# DM01x2.net
KiCad netlist of a schematic drawn in EAGLE
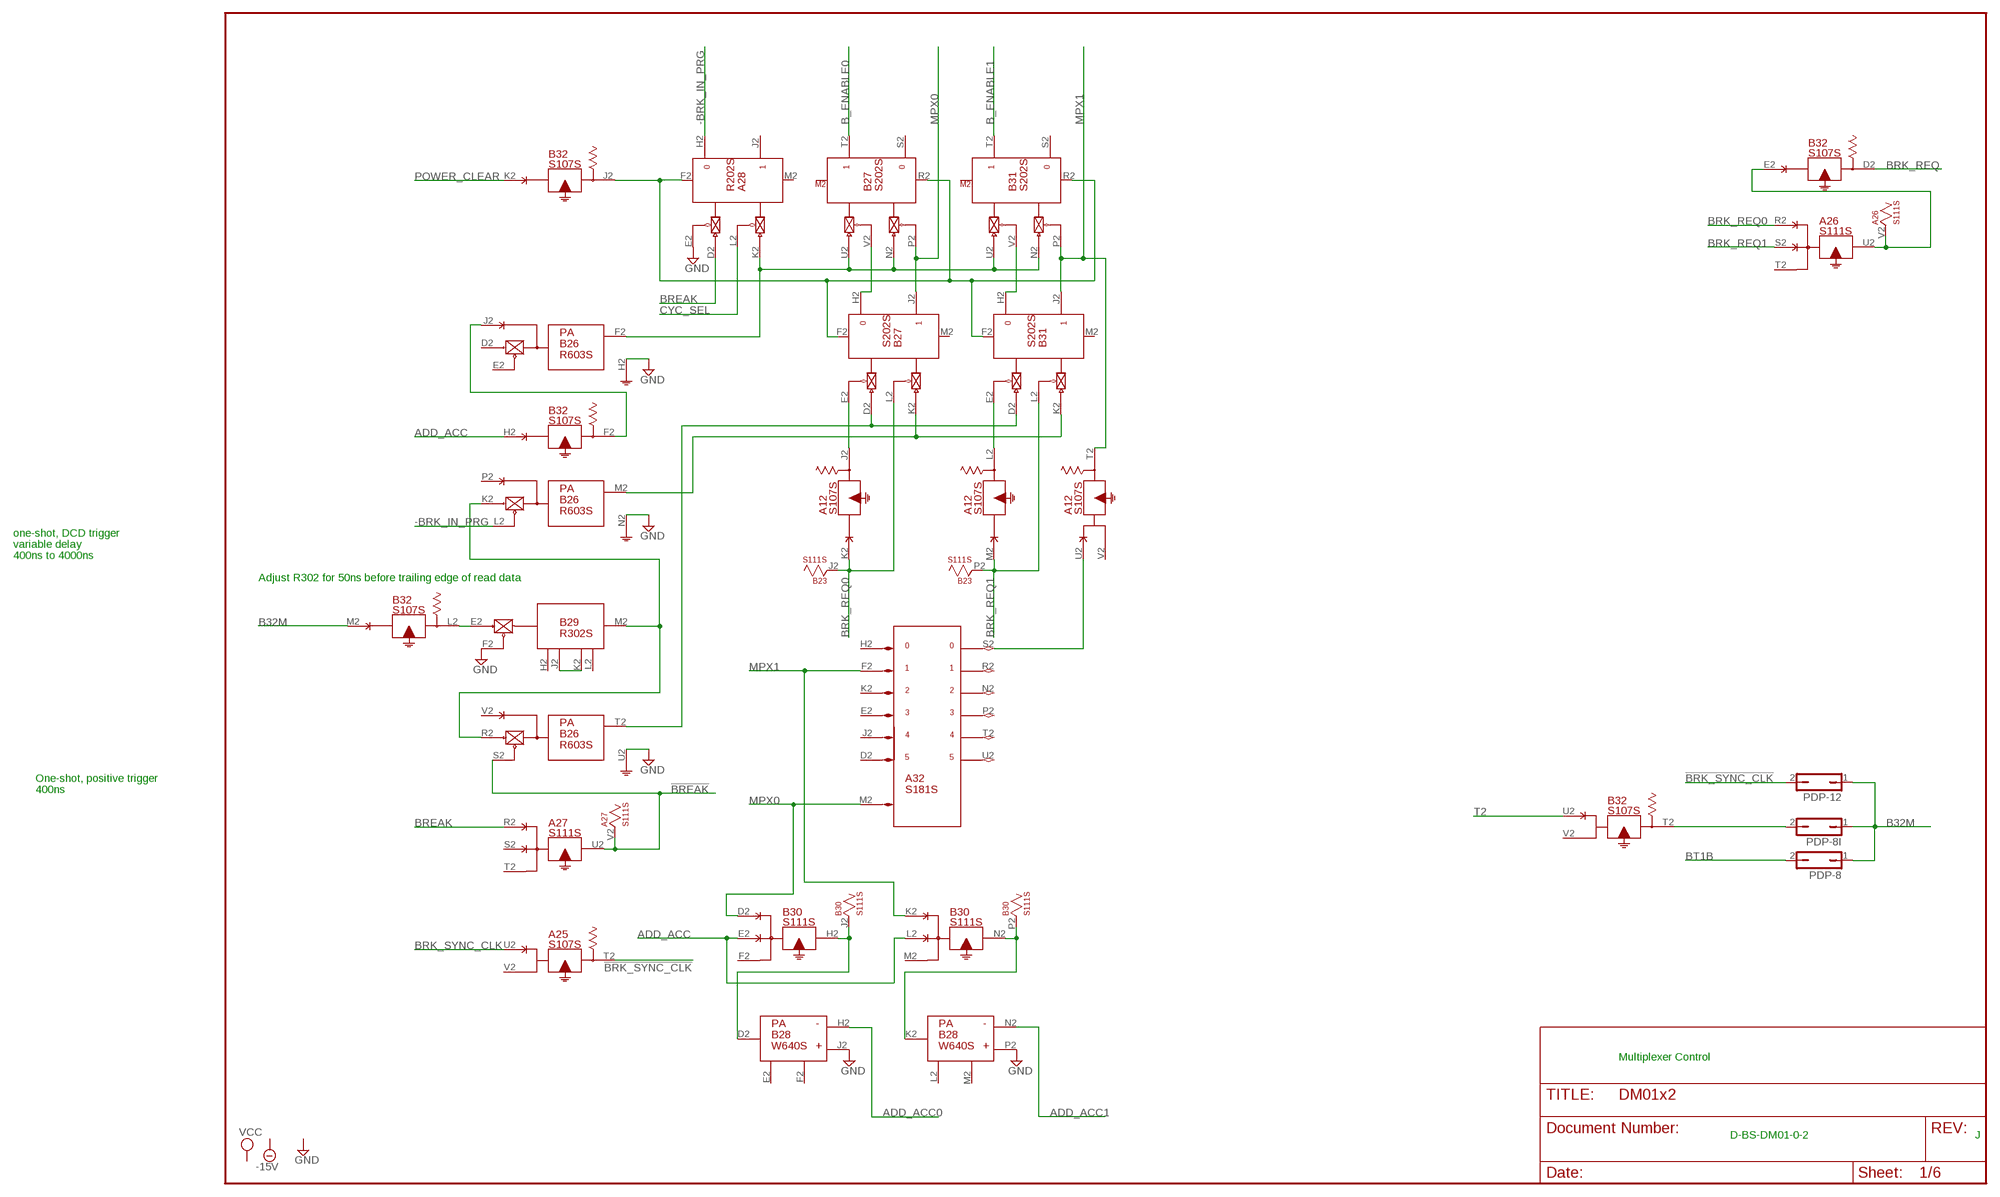
[diagram p0: schematic, sheet 1]
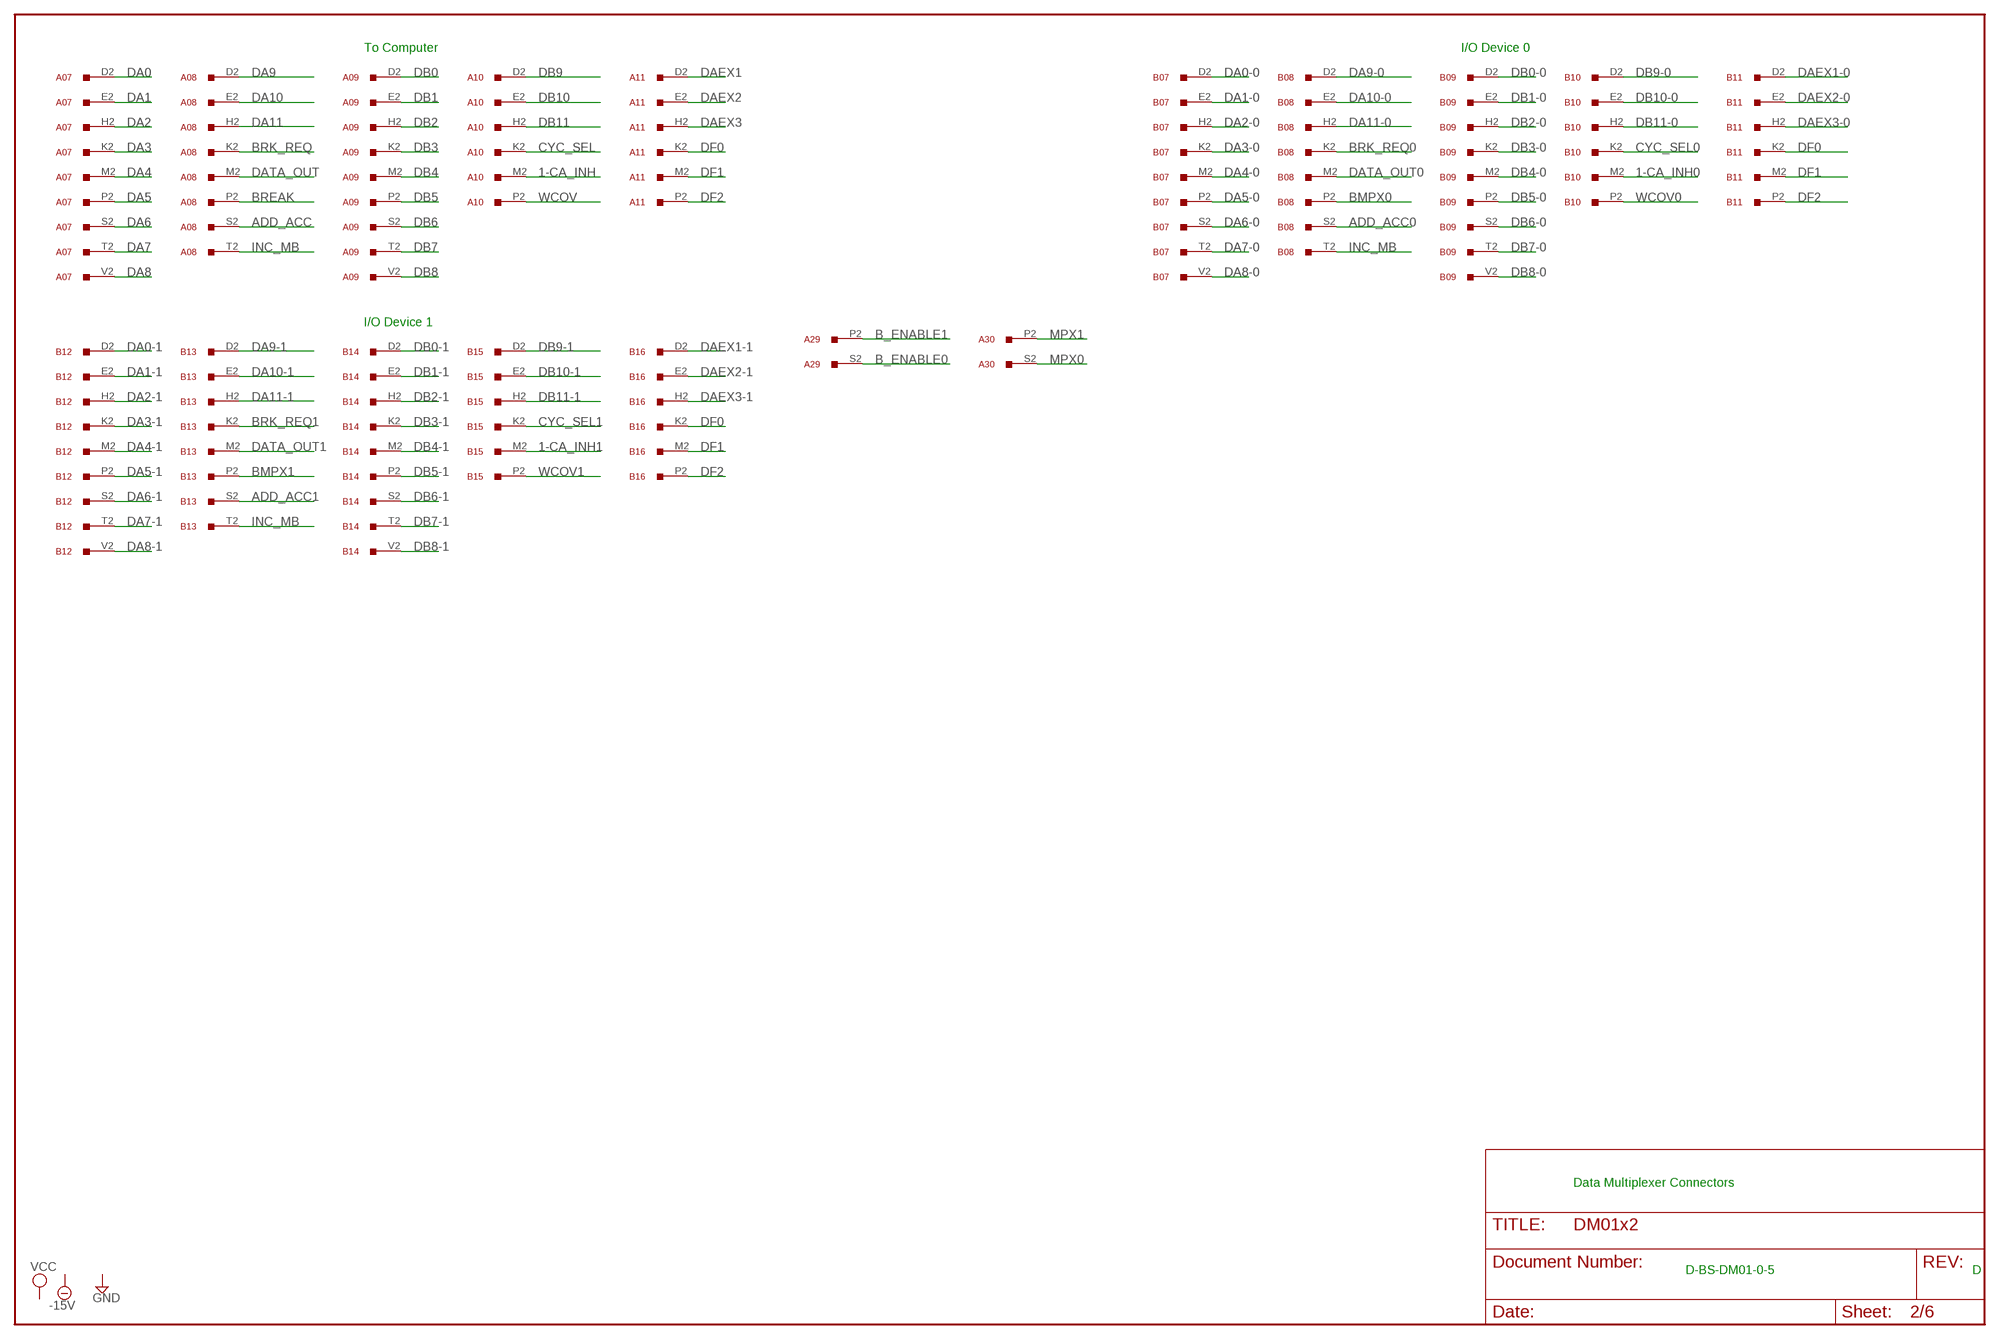
[diagram p1: schematic, sheet 2]
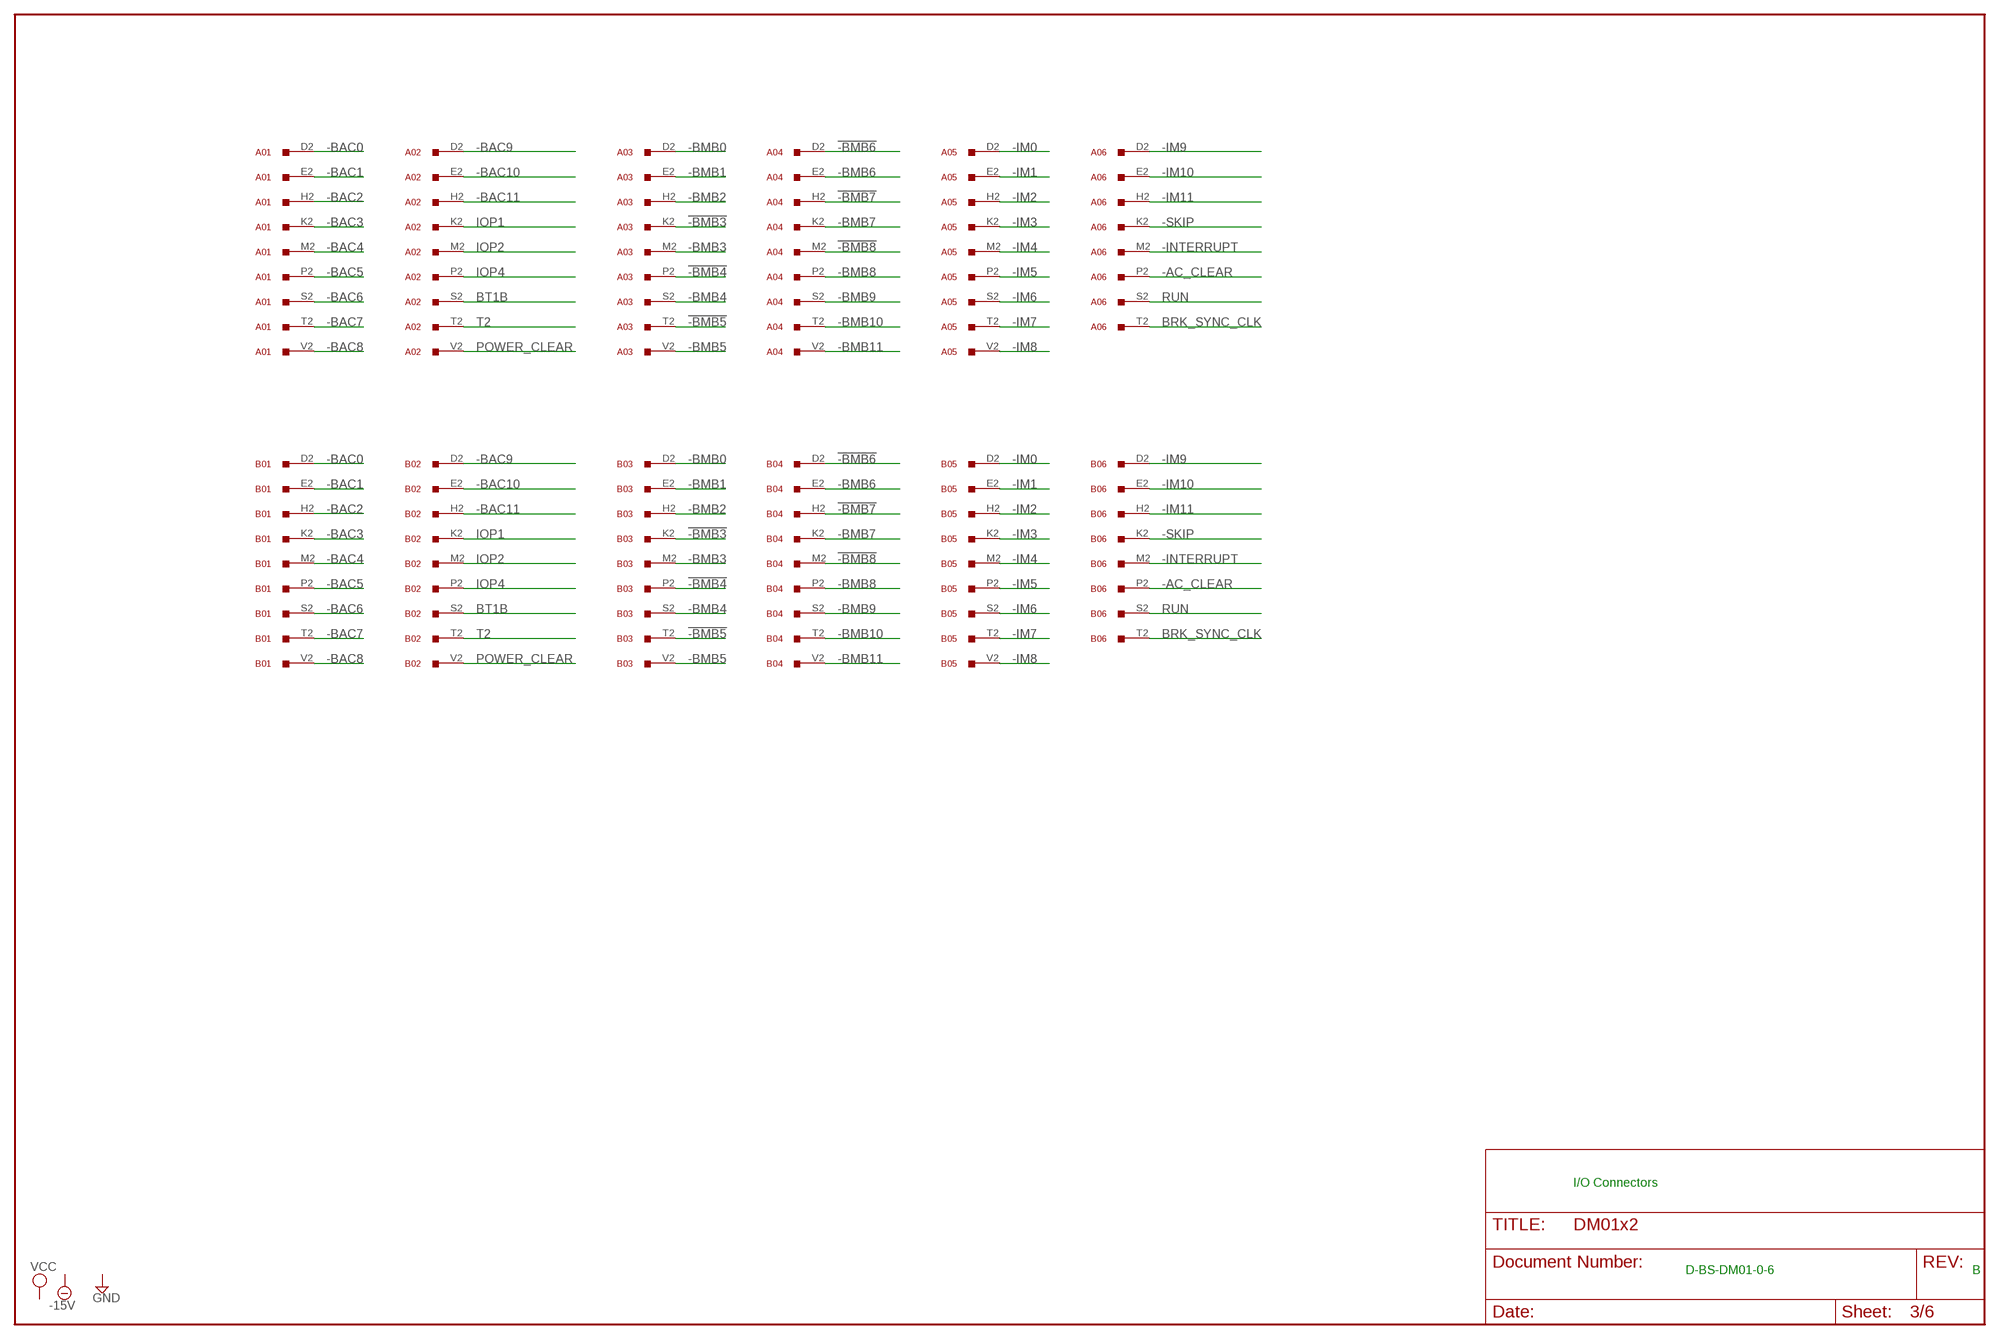
[diagram p2: schematic, sheet 3]
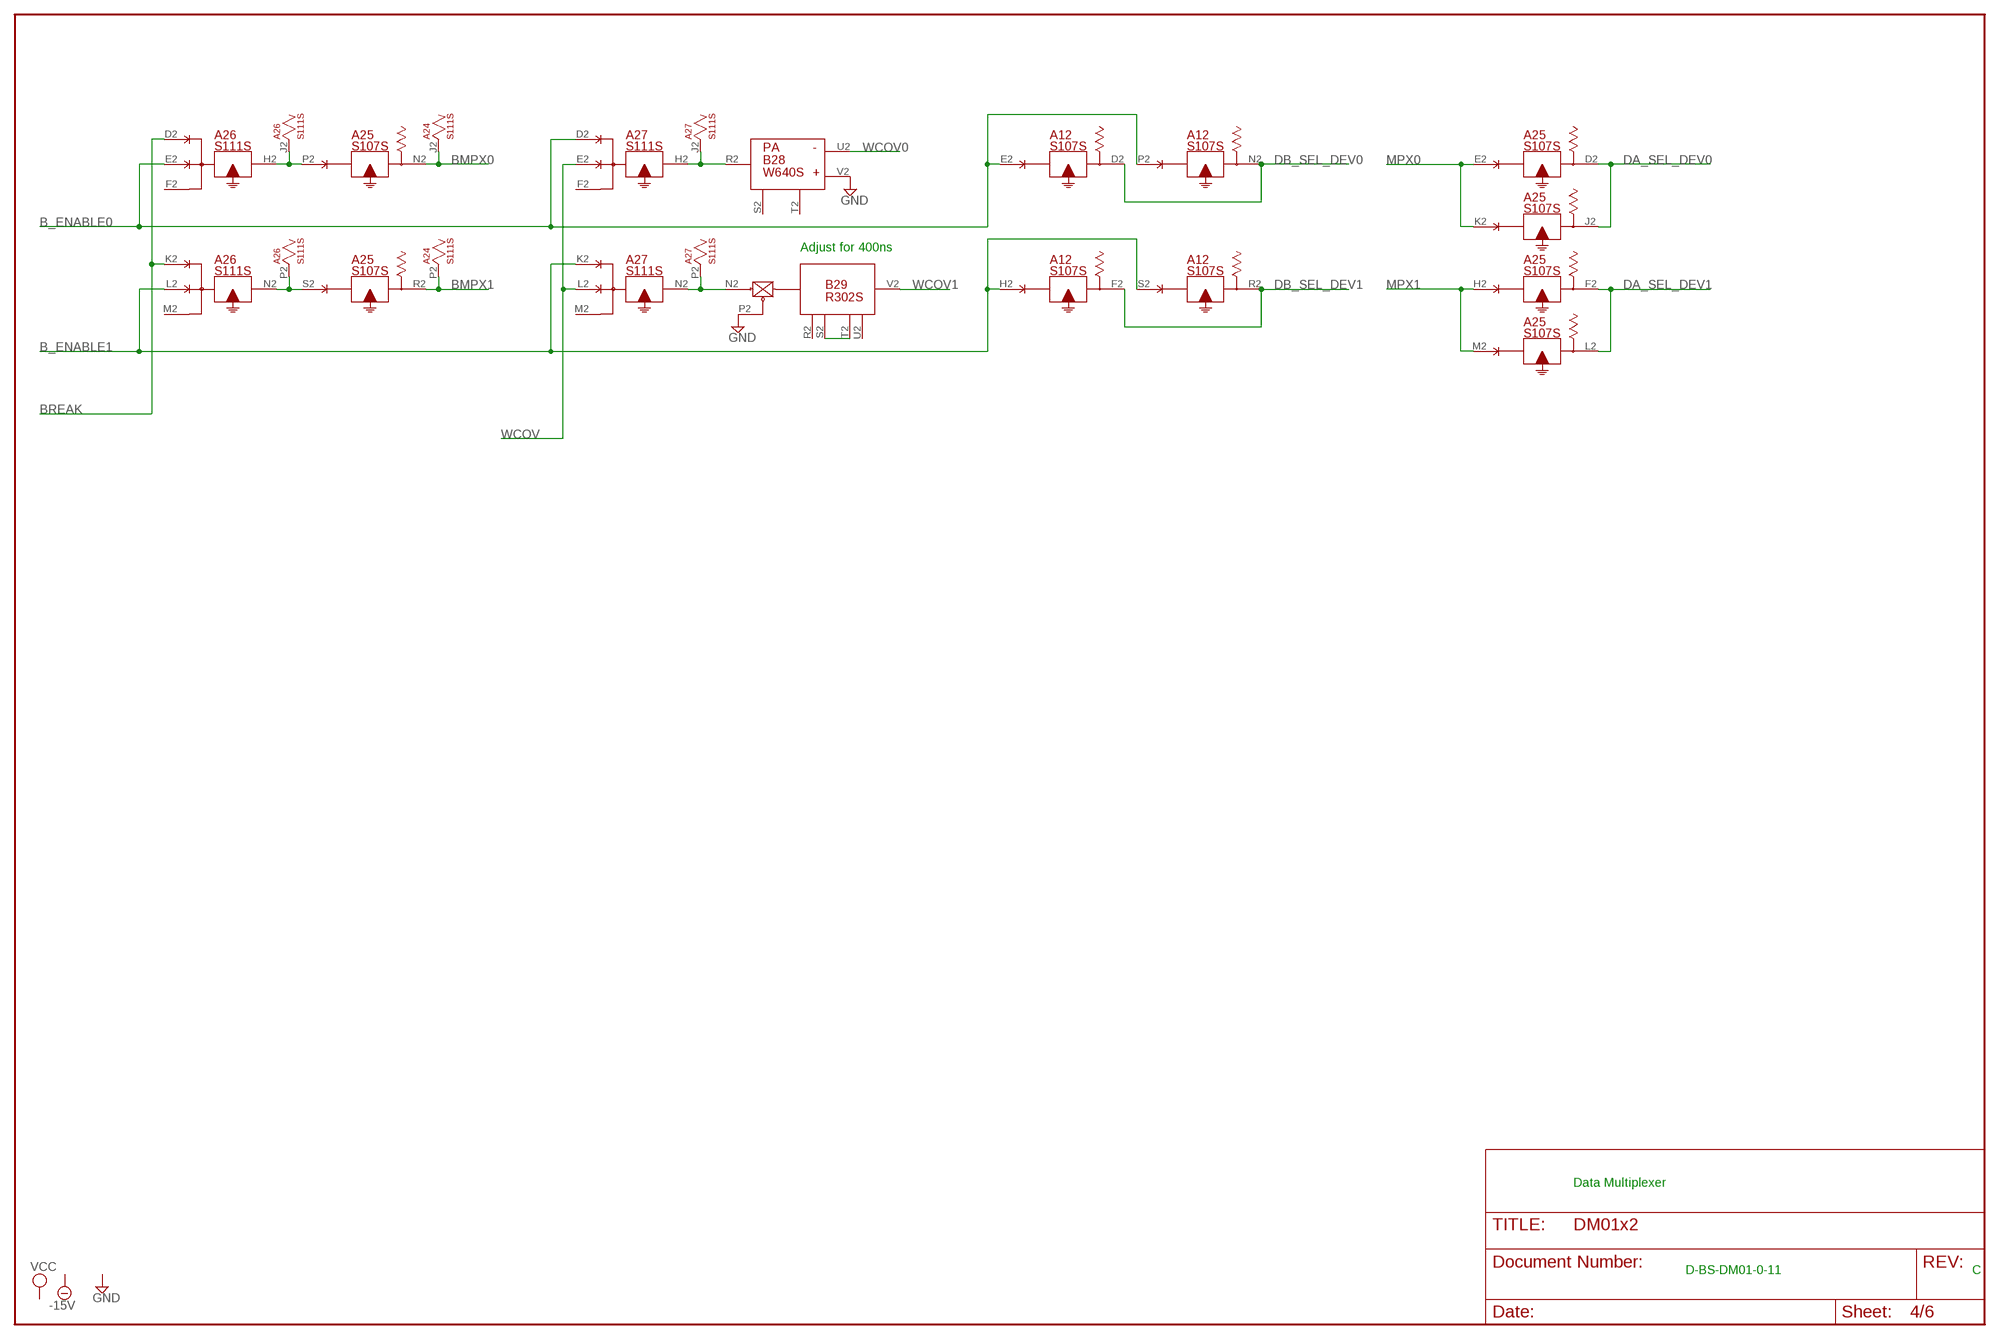
[diagram p3: schematic, sheet 4]
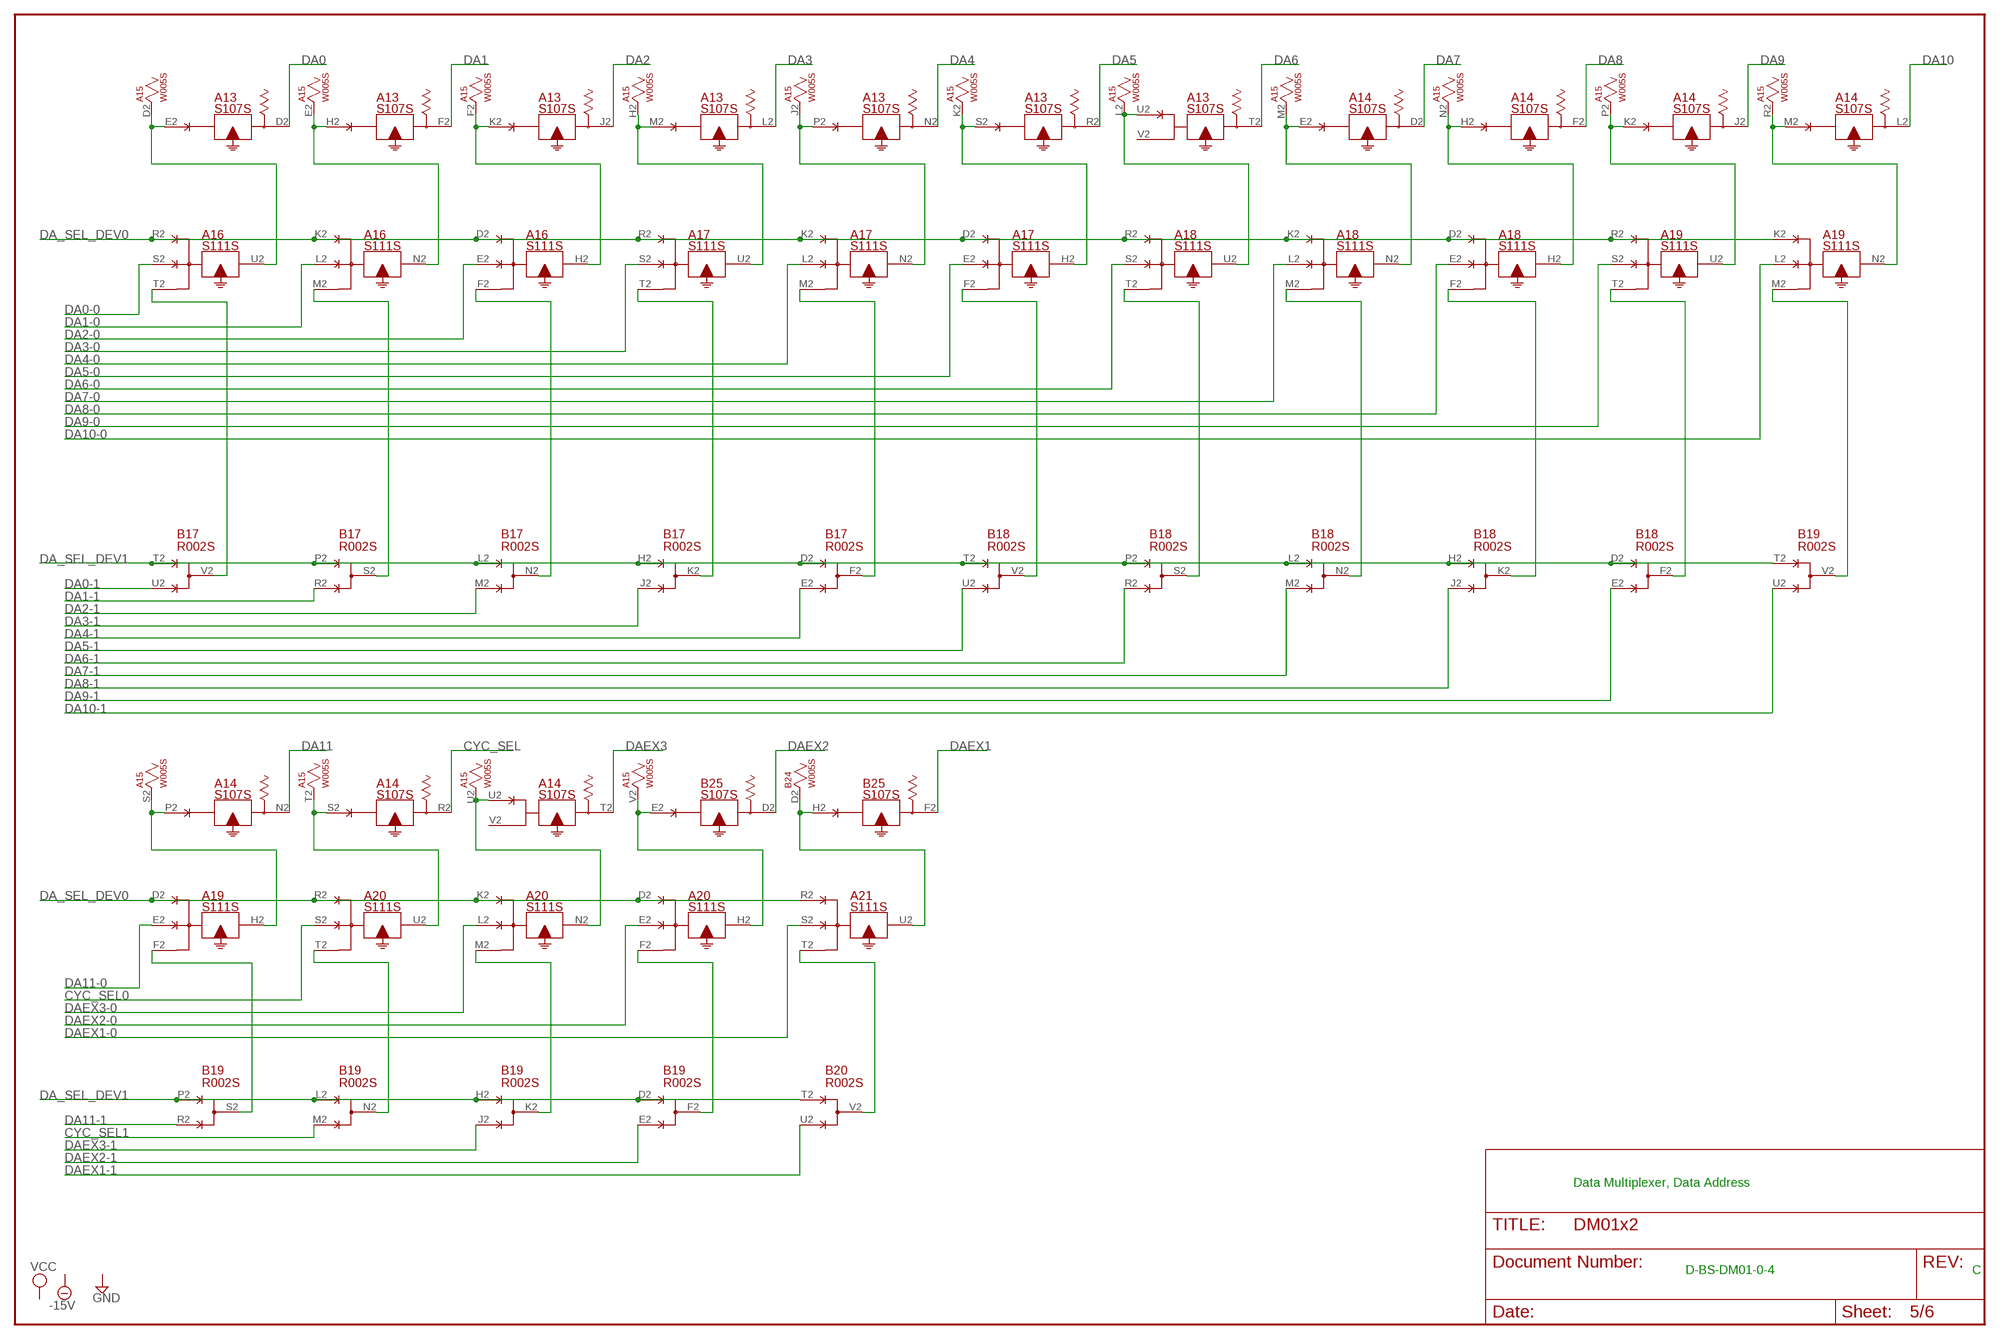
[diagram p4: schematic, sheet 5]
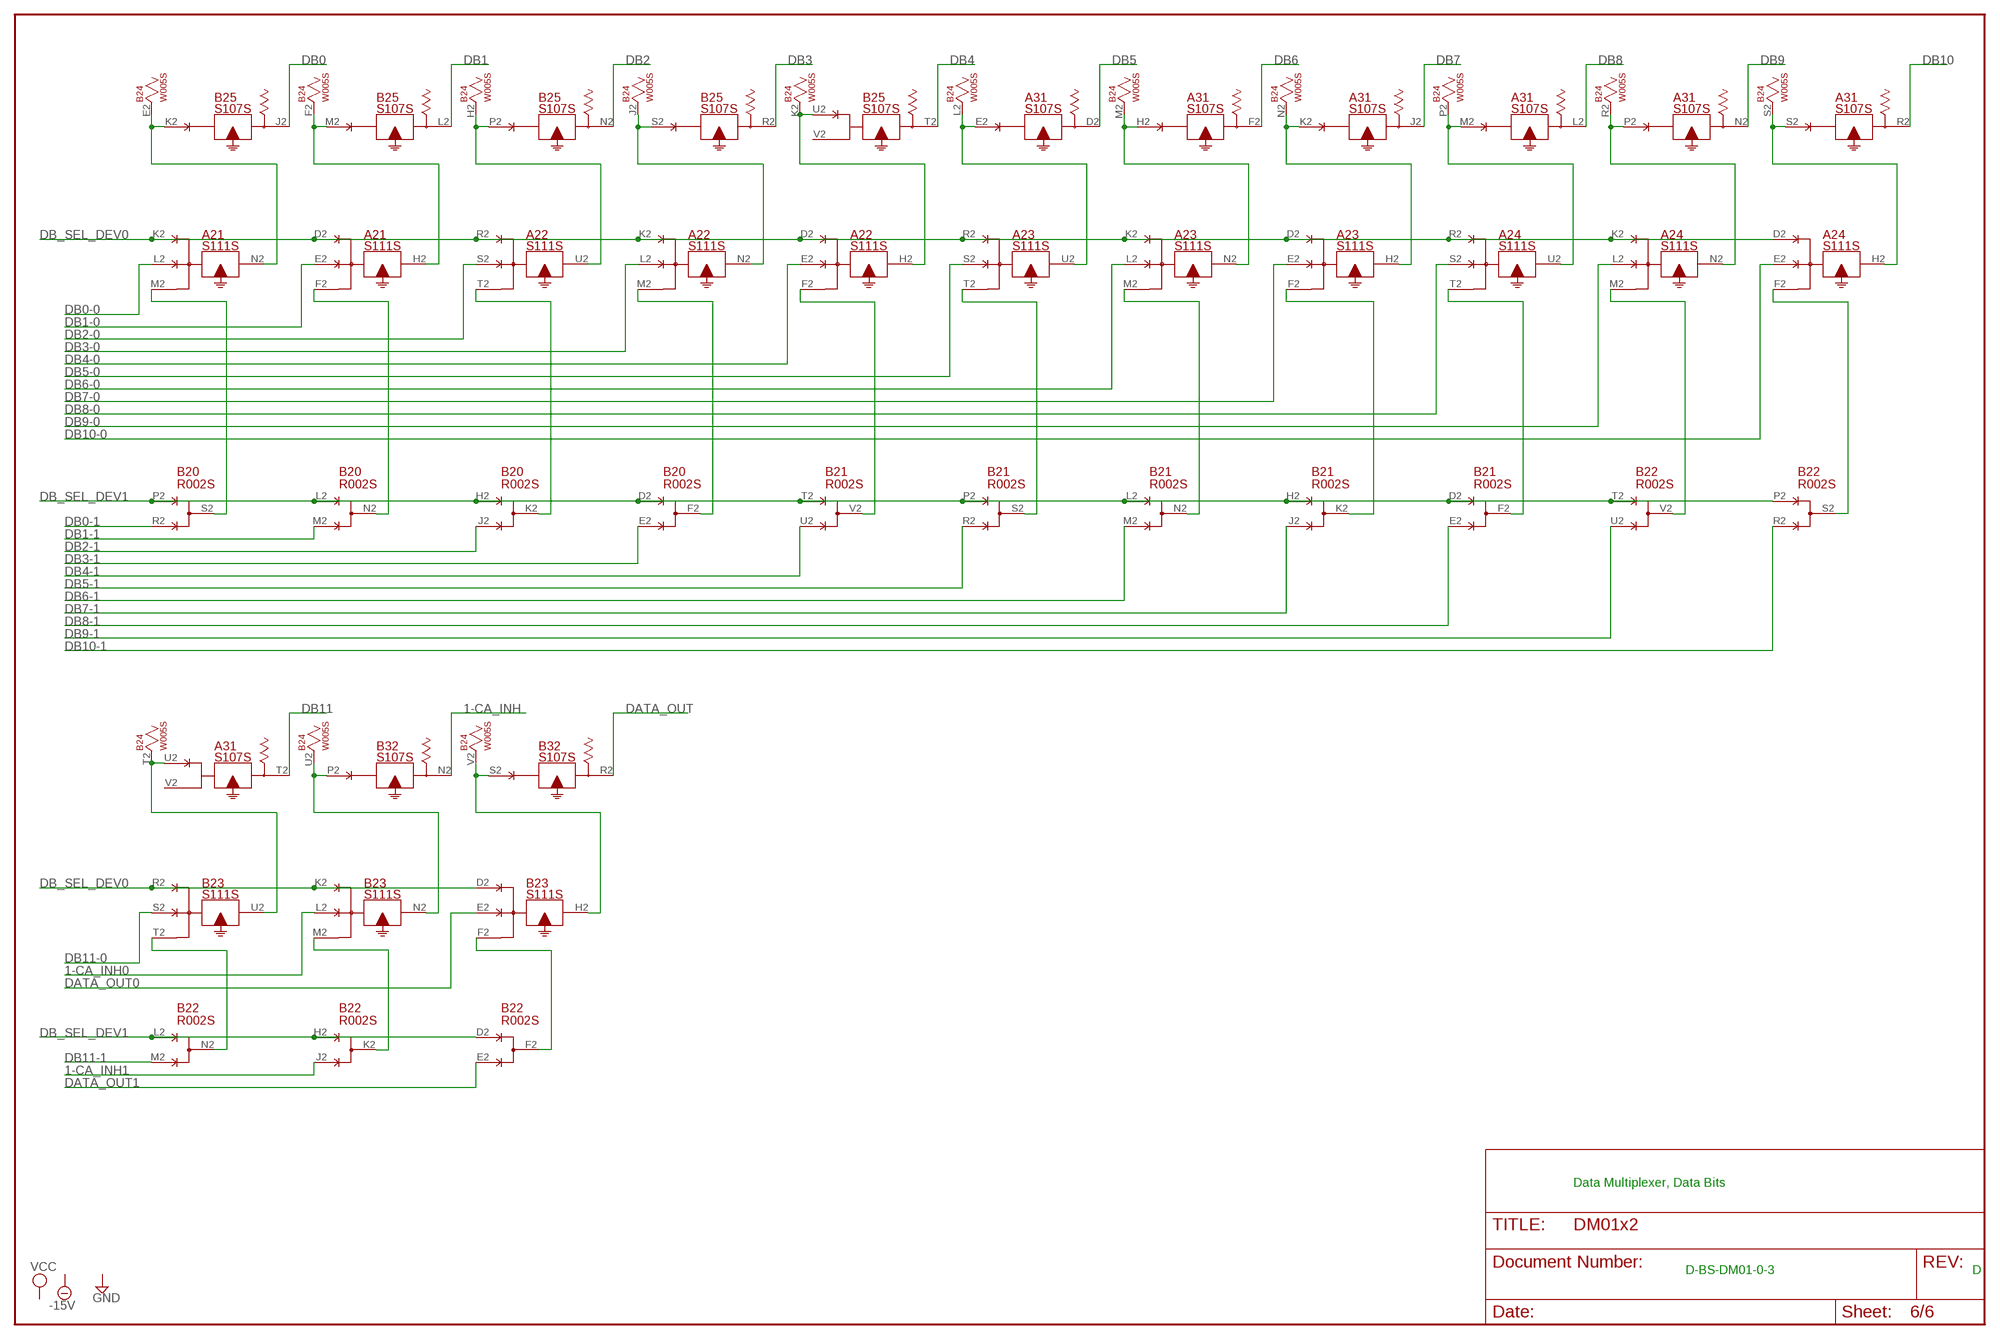
[diagram p5: schematic, sheet 6]

(export (version "E")
  (design (tool "Eeschema 10.0.6"))
  (components
    (comp (ref "A01")
      (value "W021S")
      (footprint "eagle-import:H807S")
      (libsource (lib "eagle-import") (part "W021S"))
    )
    (comp (ref "A02")
      (value "W021S")
      (footprint "eagle-import:H807S")
      (libsource (lib "eagle-import") (part "W021S"))
    )
    (comp (ref "A03")
      (value "W021S")
      (footprint "eagle-import:H807S")
      (libsource (lib "eagle-import") (part "W021S"))
    )
    (comp (ref "A04")
      (value "W021S")
      (footprint "eagle-import:H807S")
      (libsource (lib "eagle-import") (part "W021S"))
    )
    (comp (ref "A05")
      (value "W021S")
      (footprint "eagle-import:H807S")
      (libsource (lib "eagle-import") (part "W021S"))
    )
    (comp (ref "A06")
      (value "W021S")
      (footprint "eagle-import:H807S")
      (libsource (lib "eagle-import") (part "W021S"))
    )
    (comp (ref "B01")
      (value "W021S")
      (footprint "eagle-import:H807S")
      (libsource (lib "eagle-import") (part "W021S"))
    )
    (comp (ref "B02")
      (value "W021S")
      (footprint "eagle-import:H807S")
      (libsource (lib "eagle-import") (part "W021S"))
    )
    (comp (ref "B03")
      (value "W021S")
      (footprint "eagle-import:H807S")
      (libsource (lib "eagle-import") (part "W021S"))
    )
    (comp (ref "B04")
      (value "W021S")
      (footprint "eagle-import:H807S")
      (libsource (lib "eagle-import") (part "W021S"))
    )
    (comp (ref "B05")
      (value "W021S")
      (footprint "eagle-import:H807S")
      (libsource (lib "eagle-import") (part "W021S"))
    )
    (comp (ref "B06")
      (value "W021S")
      (footprint "eagle-import:H807S")
      (libsource (lib "eagle-import") (part "W021S"))
    )
    (comp (ref "A12")
      (value "S107S")
      (footprint "eagle-import:H807S")
      (libsource (lib "eagle-import") (part "R107S"))
    )
    (comp (ref "A25")
      (value "S107S")
      (footprint "eagle-import:H807S")
      (libsource (lib "eagle-import") (part "R107S"))
    )
    (comp (ref "A26")
      (value "S111S")
      (footprint "eagle-import:H807S")
      (libsource (lib "eagle-import") (part "R111S"))
    )
    (comp (ref "A27")
      (value "S111S")
      (footprint "eagle-import:H807S")
      (libsource (lib "eagle-import") (part "R111S"))
    )
    (comp (ref "A28")
      (value "R202S")
      (footprint "eagle-import:H807S")
      (libsource (lib "eagle-import") (part "R202S"))
    )
    (comp (ref "A32")
      (value "S181S")
      (footprint "eagle-import:H807S")
      (libsource (lib "eagle-import") (part "R181S"))
    )
    (comp (ref "B23")
      (value "S111S")
      (footprint "eagle-import:H807S")
      (libsource (lib "eagle-import") (part "R111S"))
    )
    (comp (ref "B26")
      (value "R603S")
      (footprint "eagle-import:H807S")
      (libsource (lib "eagle-import") (part "R603S"))
    )
    (comp (ref "B27")
      (value "S202S")
      (footprint "eagle-import:H807S")
      (libsource (lib "eagle-import") (part "R202S"))
    )
    (comp (ref "B28")
      (value "W640S")
      (footprint "eagle-import:H807S")
      (libsource (lib "eagle-import") (part "W640S"))
    )
    (comp (ref "B29")
      (value "R302S")
      (footprint "eagle-import:H807S")
      (libsource (lib "eagle-import") (part "R302S"))
    )
    (comp (ref "B30")
      (value "S111S")
      (footprint "eagle-import:H807S")
      (libsource (lib "eagle-import") (part "R111S"))
    )
    (comp (ref "B31")
      (value "S202S")
      (footprint "eagle-import:H807S")
      (libsource (lib "eagle-import") (part "R202S"))
    )
    (comp (ref "B32")
      (value "S107S")
      (footprint "eagle-import:H807S")
      (libsource (lib "eagle-import") (part "R107S"))
    )
    (comp (ref "PDP-8")
      (value "JP1Q")
      (footprint "eagle-import:JP1")
      (libsource (lib "eagle-import") (part "JP1Q"))
    )
    (comp (ref "PDP-8I")
      (value "JP1Q")
      (footprint "eagle-import:JP1")
      (libsource (lib "eagle-import") (part "JP1Q"))
    )
    (comp (ref "PDP-12")
      (value "JP1Q")
      (footprint "eagle-import:JP1")
      (libsource (lib "eagle-import") (part "JP1Q"))
    )
    (comp (ref "A13")
      (value "S107S")
      (footprint "eagle-import:H807S")
      (libsource (lib "eagle-import") (part "R107S"))
    )
    (comp (ref "A14")
      (value "S107S")
      (footprint "eagle-import:H807S")
      (libsource (lib "eagle-import") (part "R107S"))
    )
    (comp (ref "A15")
      (value "W005S")
      (footprint "eagle-import:H807S")
      (libsource (lib "eagle-import") (part "W005S"))
    )
    (comp (ref "A16")
      (value "S111S")
      (footprint "eagle-import:H807S")
      (libsource (lib "eagle-import") (part "R111S"))
    )
    (comp (ref "A17")
      (value "S111S")
      (footprint "eagle-import:H807S")
      (libsource (lib "eagle-import") (part "R111S"))
    )
    (comp (ref "A18")
      (value "S111S")
      (footprint "eagle-import:H807S")
      (libsource (lib "eagle-import") (part "R111S"))
    )
    (comp (ref "A19")
      (value "S111S")
      (footprint "eagle-import:H807S")
      (libsource (lib "eagle-import") (part "R111S"))
    )
    (comp (ref "A20")
      (value "S111S")
      (footprint "eagle-import:H807S")
      (libsource (lib "eagle-import") (part "R111S"))
    )
    (comp (ref "A21")
      (value "S111S")
      (footprint "eagle-import:H807S")
      (libsource (lib "eagle-import") (part "R111S"))
    )
    (comp (ref "B17")
      (value "R002S")
      (footprint "eagle-import:H807S")
      (libsource (lib "eagle-import") (part "R002S"))
    )
    (comp (ref "B18")
      (value "R002S")
      (footprint "eagle-import:H807S")
      (libsource (lib "eagle-import") (part "R002S"))
    )
    (comp (ref "B19")
      (value "R002S")
      (footprint "eagle-import:H807S")
      (libsource (lib "eagle-import") (part "R002S"))
    )
    (comp (ref "B20")
      (value "R002S")
      (footprint "eagle-import:H807S")
      (libsource (lib "eagle-import") (part "R002S"))
    )
    (comp (ref "B24")
      (value "W005S")
      (footprint "eagle-import:H807S")
      (libsource (lib "eagle-import") (part "W005S"))
    )
    (comp (ref "B25")
      (value "S107S")
      (footprint "eagle-import:H807S")
      (libsource (lib "eagle-import") (part "R107S"))
    )
    (comp (ref "A24")
      (value "S111S")
      (footprint "eagle-import:H807S")
      (libsource (lib "eagle-import") (part "R111S"))
    )
    (comp (ref "A07")
      (value "W021S")
      (footprint "eagle-import:H807S")
      (libsource (lib "eagle-import") (part "W021S"))
    )
    (comp (ref "A08")
      (value "W021S")
      (footprint "eagle-import:H807S")
      (libsource (lib "eagle-import") (part "W021S"))
    )
    (comp (ref "A09")
      (value "W021S")
      (footprint "eagle-import:H807S")
      (libsource (lib "eagle-import") (part "W021S"))
    )
    (comp (ref "A10")
      (value "W021S")
      (footprint "eagle-import:H807S")
      (libsource (lib "eagle-import") (part "W021S"))
    )
    (comp (ref "A11")
      (value "W021S")
      (footprint "eagle-import:H807S")
      (libsource (lib "eagle-import") (part "W021S"))
    )
    (comp (ref "A29")
      (value "W021S")
      (footprint "eagle-import:H807S")
      (libsource (lib "eagle-import") (part "W021S"))
    )
    (comp (ref "A30")
      (value "W021S")
      (footprint "eagle-import:H807S")
      (libsource (lib "eagle-import") (part "W021S"))
    )
    (comp (ref "B07")
      (value "W021S")
      (footprint "eagle-import:H807S")
      (libsource (lib "eagle-import") (part "W021S"))
    )
    (comp (ref "B08")
      (value "W021S")
      (footprint "eagle-import:H807S")
      (libsource (lib "eagle-import") (part "W021S"))
    )
    (comp (ref "B09")
      (value "W021S")
      (footprint "eagle-import:H807S")
      (libsource (lib "eagle-import") (part "W021S"))
    )
    (comp (ref "B10")
      (value "W021S")
      (footprint "eagle-import:H807S")
      (libsource (lib "eagle-import") (part "W021S"))
    )
    (comp (ref "B11")
      (value "W021S")
      (footprint "eagle-import:H807S")
      (libsource (lib "eagle-import") (part "W021S"))
    )
    (comp (ref "B12")
      (value "W021S")
      (footprint "eagle-import:H807S")
      (libsource (lib "eagle-import") (part "W021S"))
    )
    (comp (ref "B13")
      (value "W021S")
      (footprint "eagle-import:H807S")
      (libsource (lib "eagle-import") (part "W021S"))
    )
    (comp (ref "B14")
      (value "W021S")
      (footprint "eagle-import:H807S")
      (libsource (lib "eagle-import") (part "W021S"))
    )
    (comp (ref "B15")
      (value "W021S")
      (footprint "eagle-import:H807S")
      (libsource (lib "eagle-import") (part "W021S"))
    )
    (comp (ref "B16")
      (value "W021S")
      (footprint "eagle-import:H807S")
      (libsource (lib "eagle-import") (part "W021S"))
    )
    (comp (ref "A22")
      (value "S111S")
      (footprint "eagle-import:H807S")
      (libsource (lib "eagle-import") (part "R111S"))
    )
    (comp (ref "A23")
      (value "S111S")
      (footprint "eagle-import:H807S")
      (libsource (lib "eagle-import") (part "R111S"))
    )
    (comp (ref "A31")
      (value "S107S")
      (footprint "eagle-import:H807S")
      (libsource (lib "eagle-import") (part "R107S"))
    )
    (comp (ref "B21")
      (value "R002S")
      (footprint "eagle-import:H807S")
      (libsource (lib "eagle-import") (part "R002S"))
    )
    (comp (ref "B22")
      (value "R002S")
      (footprint "eagle-import:H807S")
      (libsource (lib "eagle-import") (part "R002S"))
    )
  )
  (nets
    (net (code "2") (name "-AC_CLEAR") (class "Default")
      (node (ref "A06") (pin "P2") (pinfunction "P$2_P2") (pintype "bidirectional"))
      (node (ref "B06") (pin "P2") (pinfunction "P$2_P2") (pintype "bidirectional"))
    )
    (net (code "3") (name "-BAC0") (class "Default")
      (node (ref "A01") (pin "D2") (pinfunction "P$2_D2") (pintype "bidirectional"))
      (node (ref "B01") (pin "D2") (pinfunction "P$2_D2") (pintype "bidirectional"))
    )
    (net (code "4") (name "-BAC1") (class "Default")
      (node (ref "A01") (pin "E2") (pinfunction "P$2_E2") (pintype "bidirectional"))
      (node (ref "B01") (pin "E2") (pinfunction "P$2_E2") (pintype "bidirectional"))
    )
    (net (code "5") (name "-BAC2") (class "Default")
      (node (ref "A01") (pin "H2") (pinfunction "P$2_H2") (pintype "bidirectional"))
      (node (ref "B01") (pin "H2") (pinfunction "P$2_H2") (pintype "bidirectional"))
    )
    (net (code "6") (name "-BAC3") (class "Default")
      (node (ref "A01") (pin "K2") (pinfunction "P$2_K2") (pintype "bidirectional"))
      (node (ref "B01") (pin "K2") (pinfunction "P$2_K2") (pintype "bidirectional"))
    )
    (net (code "7") (name "-BAC4") (class "Default")
      (node (ref "A01") (pin "M2") (pinfunction "P$2_M2") (pintype "bidirectional"))
      (node (ref "B01") (pin "M2") (pinfunction "P$2_M2") (pintype "bidirectional"))
    )
    (net (code "8") (name "-BAC5") (class "Default")
      (node (ref "A01") (pin "P2") (pinfunction "P$2_P2") (pintype "bidirectional"))
      (node (ref "B01") (pin "P2") (pinfunction "P$2_P2") (pintype "bidirectional"))
    )
    (net (code "9") (name "-BAC6") (class "Default")
      (node (ref "A01") (pin "S2") (pinfunction "P$2_S2") (pintype "bidirectional"))
      (node (ref "B01") (pin "S2") (pinfunction "P$2_S2") (pintype "bidirectional"))
    )
    (net (code "10") (name "-BAC7") (class "Default")
      (node (ref "A01") (pin "T2") (pinfunction "P$2_T2") (pintype "bidirectional"))
      (node (ref "B01") (pin "T2") (pinfunction "P$2_T2") (pintype "bidirectional"))
    )
    (net (code "11") (name "-BAC8") (class "Default")
      (node (ref "A01") (pin "V2") (pinfunction "P$2_V2") (pintype "bidirectional"))
      (node (ref "B01") (pin "V2") (pinfunction "P$2_V2") (pintype "bidirectional"))
    )
    (net (code "12") (name "-BAC9") (class "Default")
      (node (ref "A02") (pin "D2") (pinfunction "P$2_D2") (pintype "bidirectional"))
      (node (ref "B02") (pin "D2") (pinfunction "P$2_D2") (pintype "bidirectional"))
    )
    (net (code "13") (name "-BAC10") (class "Default")
      (node (ref "A02") (pin "E2") (pinfunction "P$2_E2") (pintype "bidirectional"))
      (node (ref "B02") (pin "E2") (pinfunction "P$2_E2") (pintype "bidirectional"))
    )
    (net (code "14") (name "-BAC11") (class "Default")
      (node (ref "A02") (pin "H2") (pinfunction "P$2_H2") (pintype "bidirectional"))
      (node (ref "B02") (pin "H2") (pinfunction "P$2_H2") (pintype "bidirectional"))
    )
    (net (code "15") (name "-BMB0") (class "Default")
      (node (ref "A03") (pin "D2") (pinfunction "P$2_D2") (pintype "bidirectional"))
      (node (ref "B03") (pin "D2") (pinfunction "P$2_D2") (pintype "bidirectional"))
    )
    (net (code "16") (name "-BMB1") (class "Default")
      (node (ref "A03") (pin "E2") (pinfunction "P$2_E2") (pintype "bidirectional"))
      (node (ref "B03") (pin "E2") (pinfunction "P$2_E2") (pintype "bidirectional"))
    )
    (net (code "17") (name "-BMB2") (class "Default")
      (node (ref "A03") (pin "H2") (pinfunction "P$2_H2") (pintype "bidirectional"))
      (node (ref "B03") (pin "H2") (pinfunction "P$2_H2") (pintype "bidirectional"))
    )
    (net (code "18") (name "-BMB3") (class "Default")
      (node (ref "A03") (pin "M2") (pinfunction "P$2_M2") (pintype "bidirectional"))
      (node (ref "B03") (pin "M2") (pinfunction "P$2_M2") (pintype "bidirectional"))
    )
    (net (code "19") (name "-BMB4") (class "Default")
      (node (ref "A03") (pin "S2") (pinfunction "P$2_S2") (pintype "bidirectional"))
      (node (ref "B03") (pin "S2") (pinfunction "P$2_S2") (pintype "bidirectional"))
    )
    (net (code "20") (name "-BMB5") (class "Default")
      (node (ref "A03") (pin "V2") (pinfunction "P$2_V2") (pintype "bidirectional"))
      (node (ref "B03") (pin "V2") (pinfunction "P$2_V2") (pintype "bidirectional"))
    )
    (net (code "21") (name "-BMB6") (class "Default")
      (node (ref "A04") (pin "E2") (pinfunction "P$2_E2") (pintype "bidirectional"))
      (node (ref "B04") (pin "E2") (pinfunction "P$2_E2") (pintype "bidirectional"))
    )
    (net (code "22") (name "-BMB7") (class "Default")
      (node (ref "A04") (pin "K2") (pinfunction "P$2_K2") (pintype "bidirectional"))
      (node (ref "B04") (pin "K2") (pinfunction "P$2_K2") (pintype "bidirectional"))
    )
    (net (code "23") (name "-BMB8") (class "Default")
      (node (ref "A04") (pin "P2") (pinfunction "P$2_P2") (pintype "bidirectional"))
      (node (ref "B04") (pin "P2") (pinfunction "P$2_P2") (pintype "bidirectional"))
    )
    (net (code "24") (name "-BMB9") (class "Default")
      (node (ref "A04") (pin "S2") (pinfunction "P$2_S2") (pintype "bidirectional"))
      (node (ref "B04") (pin "S2") (pinfunction "P$2_S2") (pintype "bidirectional"))
    )
    (net (code "25") (name "-BMB10") (class "Default")
      (node (ref "A04") (pin "T2") (pinfunction "P$2_T2") (pintype "bidirectional"))
      (node (ref "B04") (pin "T2") (pinfunction "P$2_T2") (pintype "bidirectional"))
    )
    (net (code "26") (name "-BMB11") (class "Default")
      (node (ref "A04") (pin "V2") (pinfunction "P$2_V2") (pintype "bidirectional"))
      (node (ref "B04") (pin "V2") (pinfunction "P$2_V2") (pintype "bidirectional"))
    )
    (net (code "27") (name "-BRK_IN_PRG") (class "Default")
      (node (ref "A28") (pin "H2") (pinfunction "0_H2") (pintype "open_collector"))
      (node (ref "B26") (pin "L2") (pinfunction "EN0_L2") (pintype "passive"))
    )
    (net (code "28") (name "-IM0") (class "Default")
      (node (ref "A05") (pin "D2") (pinfunction "P$2_D2") (pintype "bidirectional"))
      (node (ref "B05") (pin "D2") (pinfunction "P$2_D2") (pintype "bidirectional"))
    )
    (net (code "29") (name "-IM1") (class "Default")
      (node (ref "A05") (pin "E2") (pinfunction "P$2_E2") (pintype "bidirectional"))
      (node (ref "B05") (pin "E2") (pinfunction "P$2_E2") (pintype "bidirectional"))
    )
    (net (code "30") (name "-IM2") (class "Default")
      (node (ref "A05") (pin "H2") (pinfunction "P$2_H2") (pintype "bidirectional"))
      (node (ref "B05") (pin "H2") (pinfunction "P$2_H2") (pintype "bidirectional"))
    )
    (net (code "31") (name "-IM3") (class "Default")
      (node (ref "A05") (pin "K2") (pinfunction "P$2_K2") (pintype "bidirectional"))
      (node (ref "B05") (pin "K2") (pinfunction "P$2_K2") (pintype "bidirectional"))
    )
    (net (code "32") (name "-IM4") (class "Default")
      (node (ref "A05") (pin "M2") (pinfunction "P$2_M2") (pintype "bidirectional"))
      (node (ref "B05") (pin "M2") (pinfunction "P$2_M2") (pintype "bidirectional"))
    )
    (net (code "33") (name "-IM5") (class "Default")
      (node (ref "A05") (pin "P2") (pinfunction "P$2_P2") (pintype "bidirectional"))
      (node (ref "B05") (pin "P2") (pinfunction "P$2_P2") (pintype "bidirectional"))
    )
    (net (code "34") (name "-IM6") (class "Default")
      (node (ref "A05") (pin "S2") (pinfunction "P$2_S2") (pintype "bidirectional"))
      (node (ref "B05") (pin "S2") (pinfunction "P$2_S2") (pintype "bidirectional"))
    )
    (net (code "35") (name "-IM7") (class "Default")
      (node (ref "A05") (pin "T2") (pinfunction "P$2_T2") (pintype "bidirectional"))
      (node (ref "B05") (pin "T2") (pinfunction "P$2_T2") (pintype "bidirectional"))
    )
    (net (code "36") (name "-IM8") (class "Default")
      (node (ref "A05") (pin "V2") (pinfunction "P$2_V2") (pintype "bidirectional"))
      (node (ref "B05") (pin "V2") (pinfunction "P$2_V2") (pintype "bidirectional"))
    )
    (net (code "37") (name "-IM9") (class "Default")
      (node (ref "A06") (pin "D2") (pinfunction "P$2_D2") (pintype "bidirectional"))
      (node (ref "B06") (pin "D2") (pinfunction "P$2_D2") (pintype "bidirectional"))
    )
    (net (code "38") (name "-IM10") (class "Default")
      (node (ref "A06") (pin "E2") (pinfunction "P$2_E2") (pintype "bidirectional"))
      (node (ref "B06") (pin "E2") (pinfunction "P$2_E2") (pintype "bidirectional"))
    )
    (net (code "39") (name "-IM11") (class "Default")
      (node (ref "A06") (pin "H2") (pinfunction "P$2_H2") (pintype "bidirectional"))
      (node (ref "B06") (pin "H2") (pinfunction "P$2_H2") (pintype "bidirectional"))
    )
    (net (code "40") (name "-INTERRUPT") (class "Default")
      (node (ref "A06") (pin "M2") (pinfunction "P$2_M2") (pintype "bidirectional"))
      (node (ref "B06") (pin "M2") (pinfunction "P$2_M2") (pintype "bidirectional"))
    )
    (net (code "41") (name "-SKIP") (class "Default")
      (node (ref "A06") (pin "K2") (pinfunction "P$2_K2") (pintype "bidirectional"))
      (node (ref "B06") (pin "K2") (pinfunction "P$2_K2") (pintype "bidirectional"))
    )
    (net (code "42") (name "1-CA_INH") (class "Default")
      (node (ref "A10") (pin "M2") (pinfunction "P$2_M2") (pintype "bidirectional"))
      (node (ref "B32") (pin "N2") (pinfunction "O$1_N2") (pintype "open_collector"))
    )
    (net (code "43") (name "1-CA_INH0") (class "Default")
      (node (ref "B10") (pin "M2") (pinfunction "P$2_M2") (pintype "bidirectional"))
      (node (ref "B23") (pin "L2") (pinfunction "I$2_L2") (pintype "input"))
    )
    (net (code "44") (name "1-CA_INH1") (class "Default")
      (node (ref "B15") (pin "M2") (pinfunction "P$2_M2") (pintype "bidirectional"))
      (node (ref "B22") (pin "J2") (pinfunction "E_J2") (pintype "input"))
    )
    (net (code "45") (name "ADD_ACC") (class "Default")
      (node (ref "A08") (pin "S2") (pinfunction "P$2_S2") (pintype "bidirectional"))
      (node (ref "B30") (pin "E2") (pinfunction "I$2_E2") (pintype "input"))
      (node (ref "B30") (pin "L2") (pinfunction "I$2_L2") (pintype "input"))
      (node (ref "B32") (pin "H2") (pinfunction "I$1_H2") (pintype "input"))
    )
    (net (code "46") (name "ADD_ACC0") (class "Default")
      (node (ref "B08") (pin "S2") (pinfunction "P$2_S2") (pintype "bidirectional"))
      (node (ref "B28") (pin "H2") (pinfunction "H_H2") (pintype "output"))
    )
    (net (code "47") (name "ADD_ACC1") (class "Default")
      (node (ref "B13") (pin "S2") (pinfunction "P$2_S2") (pintype "bidirectional"))
      (node (ref "B28") (pin "N2") (pinfunction "H_N2") (pintype "output"))
    )
    (net (code "48") (name "B32M") (class "Default")
      (node (ref "B32") (pin "M2") (pinfunction "I$1_M2") (pintype "input"))
      (node (ref "PDP-12") (pin "1") (pinfunction "1_1") (pintype "passive"))
      (node (ref "PDP-8") (pin "1") (pinfunction "1_1") (pintype "passive"))
      (node (ref "PDP-8I") (pin "1") (pinfunction "1_1") (pintype "passive"))
    )
    (net (code "49") (name "BMPX0") (class "Default")
      (node (ref "A24") (pin "J2") (pinfunction "P$1_J2") (pintype "passive"))
      (node (ref "A25") (pin "N2") (pinfunction "O$1_N2") (pintype "open_collector"))
      (node (ref "B08") (pin "P2") (pinfunction "P$2_P2") (pintype "bidirectional"))
    )
    (net (code "50") (name "BMPX1") (class "Default")
      (node (ref "A24") (pin "P2") (pinfunction "P$1_P2") (pintype "passive"))
      (node (ref "A25") (pin "R2") (pinfunction "O$1_R2") (pintype "open_collector"))
      (node (ref "B13") (pin "P2") (pinfunction "P$2_P2") (pintype "bidirectional"))
    )
    (net (code "51") (name "BREAK") (class "Default")
      (node (ref "A08") (pin "P2") (pinfunction "P$2_P2") (pintype "bidirectional"))
      (node (ref "A26") (pin "D2") (pinfunction "I$1_D2") (pintype "input"))
      (node (ref "A26") (pin "K2") (pinfunction "I$1_K2") (pintype "input"))
      (node (ref "A27") (pin "R2") (pinfunction "I$1_R2") (pintype "input"))
      (node (ref "A28") (pin "D2") (pinfunction "PU0_D2") (pintype "input"))
    )
    (net (code "52") (name "BRK_REQ") (class "Default")
      (node (ref "A08") (pin "K2") (pinfunction "P$2_K2") (pintype "bidirectional"))
      (node (ref "B32") (pin "D2") (pinfunction "O$1_D2") (pintype "open_collector"))
    )
    (net (code "53") (name "BRK_REQ0") (class "Default")
      (node (ref "A12") (pin "K2") (pinfunction "I$1_K2") (pintype "input"))
      (node (ref "A26") (pin "R2") (pinfunction "I$1_R2") (pintype "input"))
      (node (ref "B08") (pin "K2") (pinfunction "P$2_K2") (pintype "bidirectional"))
      (node (ref "B23") (pin "J2") (pinfunction "P$1_J2") (pintype "passive"))
      (node (ref "B27") (pin "L2") (pinfunction "EN1_L2") (pintype "input"))
    )
    (net (code "54") (name "BRK_REQ1") (class "Default")
      (node (ref "A12") (pin "M2") (pinfunction "I$1_M2") (pintype "input"))
      (node (ref "A26") (pin "S2") (pinfunction "I$2_S2") (pintype "input"))
      (node (ref "B13") (pin "K2") (pinfunction "P$2_K2") (pintype "bidirectional"))
      (node (ref "B23") (pin "P2") (pinfunction "P$1_P2") (pintype "passive"))
      (node (ref "B31") (pin "L2") (pinfunction "EN1_L2") (pintype "input"))
    )
    (net (code "55") (name "BRK_SYNC_CLK") (class "Default")
      (node (ref "A06") (pin "T2") (pinfunction "P$2_T2") (pintype "bidirectional"))
      (node (ref "A25") (pin "U2") (pinfunction "I$1_U2") (pintype "input"))
      (node (ref "B06") (pin "T2") (pinfunction "P$2_T2") (pintype "bidirectional"))
    )
    (net (code "56") (name "BT1B") (class "Default")
      (node (ref "A02") (pin "S2") (pinfunction "P$2_S2") (pintype "bidirectional"))
      (node (ref "B02") (pin "S2") (pinfunction "P$2_S2") (pintype "bidirectional"))
      (node (ref "PDP-8") (pin "2") (pinfunction "2_2") (pintype "passive"))
    )
    (net (code "57") (name "B_ENABLE0") (class "Default")
      (node (ref "A12") (pin "E2") (pinfunction "I$1_E2") (pintype "input"))
      (node (ref "A12") (pin "P2") (pinfunction "I$1_P2") (pintype "input"))
      (node (ref "A26") (pin "E2") (pinfunction "I$2_E2") (pintype "input"))
      (node (ref "A27") (pin "D2") (pinfunction "I$1_D2") (pintype "input"))
      (node (ref "A29") (pin "S2") (pinfunction "P$2_S2") (pintype "bidirectional"))
      (node (ref "B27") (pin "T2") (pinfunction "1_T2") (pintype "open_collector"))
    )
    (net (code "58") (name "B_ENABLE1") (class "Default")
      (node (ref "A12") (pin "H2") (pinfunction "I$1_H2") (pintype "input"))
      (node (ref "A12") (pin "S2") (pinfunction "I$1_S2") (pintype "input"))
      (node (ref "A26") (pin "L2") (pinfunction "I$2_L2") (pintype "input"))
      (node (ref "A27") (pin "K2") (pinfunction "I$1_K2") (pintype "input"))
      (node (ref "A29") (pin "P2") (pinfunction "P$2_P2") (pintype "bidirectional"))
      (node (ref "B31") (pin "T2") (pinfunction "1_T2") (pintype "open_collector"))
    )
    (net (code "59") (name "CYC_SEL") (class "Default")
      (node (ref "A10") (pin "K2") (pinfunction "P$2_K2") (pintype "bidirectional"))
      (node (ref "A14") (pin "R2") (pinfunction "O$1_R2") (pintype "open_collector"))
      (node (ref "A28") (pin "L2") (pinfunction "EN1_L2") (pintype "input"))
    )
    (net (code "60") (name "CYC_SEL0") (class "Default")
      (node (ref "A20") (pin "S2") (pinfunction "I$2_S2") (pintype "input"))
      (node (ref "B10") (pin "K2") (pinfunction "P$2_K2") (pintype "bidirectional"))
    )
    (net (code "61") (name "CYC_SEL1") (class "Default")
      (node (ref "B15") (pin "K2") (pinfunction "P$2_K2") (pintype "bidirectional"))
      (node (ref "B19") (pin "M2") (pinfunction "E_M2") (pintype "input"))
    )
    (net (code "62") (name "DA0") (class "Default")
      (node (ref "A07") (pin "D2") (pinfunction "P$2_D2") (pintype "bidirectional"))
      (node (ref "A13") (pin "D2") (pinfunction "O$1_D2") (pintype "open_collector"))
    )
    (net (code "63") (name "DA0-0") (class "Default")
      (node (ref "A16") (pin "S2") (pinfunction "I$2_S2") (pintype "input"))
      (node (ref "B07") (pin "D2") (pinfunction "P$2_D2") (pintype "bidirectional"))
    )
    (net (code "64") (name "DA0-1") (class "Default")
      (node (ref "B12") (pin "D2") (pinfunction "P$2_D2") (pintype "bidirectional"))
      (node (ref "B17") (pin "U2") (pinfunction "E_U2") (pintype "input"))
    )
    (net (code "65") (name "DA1") (class "Default")
      (node (ref "A07") (pin "E2") (pinfunction "P$2_E2") (pintype "bidirectional"))
      (node (ref "A13") (pin "F2") (pinfunction "O$1_F2") (pintype "open_collector"))
    )
    (net (code "66") (name "DA1-0") (class "Default")
      (node (ref "A16") (pin "L2") (pinfunction "I$2_L2") (pintype "input"))
      (node (ref "B07") (pin "E2") (pinfunction "P$2_E2") (pintype "bidirectional"))
    )
    (net (code "67") (name "DA1-1") (class "Default")
      (node (ref "B12") (pin "E2") (pinfunction "P$2_E2") (pintype "bidirectional"))
      (node (ref "B17") (pin "R2") (pinfunction "E_R2") (pintype "input"))
    )
    (net (code "68") (name "DA2") (class "Default")
      (node (ref "A07") (pin "H2") (pinfunction "P$2_H2") (pintype "bidirectional"))
      (node (ref "A13") (pin "J2") (pinfunction "O$1_J2") (pintype "open_collector"))
    )
    (net (code "69") (name "DA2-0") (class "Default")
      (node (ref "A16") (pin "E2") (pinfunction "I$2_E2") (pintype "input"))
      (node (ref "B07") (pin "H2") (pinfunction "P$2_H2") (pintype "bidirectional"))
    )
    (net (code "70") (name "DA2-1") (class "Default")
      (node (ref "B12") (pin "H2") (pinfunction "P$2_H2") (pintype "bidirectional"))
      (node (ref "B17") (pin "M2") (pinfunction "E_M2") (pintype "input"))
    )
    (net (code "71") (name "DA3") (class "Default")
      (node (ref "A07") (pin "K2") (pinfunction "P$2_K2") (pintype "bidirectional"))
      (node (ref "A13") (pin "L2") (pinfunction "O$1_L2") (pintype "open_collector"))
    )
    (net (code "72") (name "DA3-0") (class "Default")
      (node (ref "A17") (pin "S2") (pinfunction "I$2_S2") (pintype "input"))
      (node (ref "B07") (pin "K2") (pinfunction "P$2_K2") (pintype "bidirectional"))
    )
    (net (code "73") (name "DA3-1") (class "Default")
      (node (ref "B12") (pin "K2") (pinfunction "P$2_K2") (pintype "bidirectional"))
      (node (ref "B17") (pin "J2") (pinfunction "E_J2") (pintype "input"))
    )
    (net (code "74") (name "DA4") (class "Default")
      (node (ref "A07") (pin "M2") (pinfunction "P$2_M2") (pintype "bidirectional"))
      (node (ref "A13") (pin "N2") (pinfunction "O$1_N2") (pintype "open_collector"))
    )
    (net (code "75") (name "DA4-0") (class "Default")
      (node (ref "A17") (pin "L2") (pinfunction "I$2_L2") (pintype "input"))
      (node (ref "B07") (pin "M2") (pinfunction "P$2_M2") (pintype "bidirectional"))
    )
    (net (code "76") (name "DA4-1") (class "Default")
      (node (ref "B12") (pin "M2") (pinfunction "P$2_M2") (pintype "bidirectional"))
      (node (ref "B17") (pin "E2") (pinfunction "E_E2") (pintype "input"))
    )
    (net (code "77") (name "DA5") (class "Default")
      (node (ref "A07") (pin "P2") (pinfunction "P$2_P2") (pintype "bidirectional"))
      (node (ref "A13") (pin "R2") (pinfunction "O$1_R2") (pintype "open_collector"))
    )
    (net (code "78") (name "DA5-0") (class "Default")
      (node (ref "A17") (pin "E2") (pinfunction "I$2_E2") (pintype "input"))
      (node (ref "B07") (pin "P2") (pinfunction "P$2_P2") (pintype "bidirectional"))
    )
    (net (code "79") (name "DA5-1") (class "Default")
      (node (ref "B12") (pin "P2") (pinfunction "P$2_P2") (pintype "bidirectional"))
      (node (ref "B18") (pin "U2") (pinfunction "E_U2") (pintype "input"))
    )
    (net (code "80") (name "DA6") (class "Default")
      (node (ref "A07") (pin "S2") (pinfunction "P$2_S2") (pintype "bidirectional"))
      (node (ref "A13") (pin "T2") (pinfunction "O$1_T2") (pintype "open_collector"))
    )
    (net (code "81") (name "DA6-0") (class "Default")
      (node (ref "A18") (pin "S2") (pinfunction "I$2_S2") (pintype "input"))
      (node (ref "B07") (pin "S2") (pinfunction "P$2_S2") (pintype "bidirectional"))
    )
    (net (code "82") (name "DA6-1") (class "Default")
      (node (ref "B12") (pin "S2") (pinfunction "P$2_S2") (pintype "bidirectional"))
      (node (ref "B18") (pin "R2") (pinfunction "E_R2") (pintype "input"))
    )
    (net (code "83") (name "DA7") (class "Default")
      (node (ref "A07") (pin "T2") (pinfunction "P$2_T2") (pintype "bidirectional"))
      (node (ref "A14") (pin "D2") (pinfunction "O$1_D2") (pintype "open_collector"))
    )
    (net (code "84") (name "DA7-0") (class "Default")
      (node (ref "A18") (pin "L2") (pinfunction "I$2_L2") (pintype "input"))
      (node (ref "B07") (pin "T2") (pinfunction "P$2_T2") (pintype "bidirectional"))
    )
    (net (code "85") (name "DA7-1") (class "Default")
      (node (ref "B12") (pin "T2") (pinfunction "P$2_T2") (pintype "bidirectional"))
      (node (ref "B18") (pin "M2") (pinfunction "E_M2") (pintype "input"))
    )
    (net (code "86") (name "DA8") (class "Default")
      (node (ref "A07") (pin "V2") (pinfunction "P$2_V2") (pintype "bidirectional"))
      (node (ref "A14") (pin "F2") (pinfunction "O$1_F2") (pintype "open_collector"))
    )
    (net (code "87") (name "DA8-0") (class "Default")
      (node (ref "A18") (pin "E2") (pinfunction "I$2_E2") (pintype "input"))
      (node (ref "B07") (pin "V2") (pinfunction "P$2_V2") (pintype "bidirectional"))
    )
    (net (code "88") (name "DA8-1") (class "Default")
      (node (ref "B12") (pin "V2") (pinfunction "P$2_V2") (pintype "bidirectional"))
      (node (ref "B18") (pin "J2") (pinfunction "E_J2") (pintype "input"))
    )
    (net (code "89") (name "DA9") (class "Default")
      (node (ref "A08") (pin "D2") (pinfunction "P$2_D2") (pintype "bidirectional"))
      (node (ref "A14") (pin "J2") (pinfunction "O$1_J2") (pintype "open_collector"))
    )
    (net (code "90") (name "DA9-0") (class "Default")
      (node (ref "A19") (pin "S2") (pinfunction "I$2_S2") (pintype "input"))
      (node (ref "B08") (pin "D2") (pinfunction "P$2_D2") (pintype "bidirectional"))
    )
    (net (code "91") (name "DA9-1") (class "Default")
      (node (ref "B13") (pin "D2") (pinfunction "P$2_D2") (pintype "bidirectional"))
      (node (ref "B18") (pin "E2") (pinfunction "E_E2") (pintype "input"))
    )
    (net (code "92") (name "DA10") (class "Default")
      (node (ref "A08") (pin "E2") (pinfunction "P$2_E2") (pintype "bidirectional"))
      (node (ref "A14") (pin "L2") (pinfunction "O$1_L2") (pintype "open_collector"))
    )
    (net (code "93") (name "DA10-0") (class "Default")
      (node (ref "A19") (pin "L2") (pinfunction "I$2_L2") (pintype "input"))
      (node (ref "B08") (pin "E2") (pinfunction "P$2_E2") (pintype "bidirectional"))
    )
    (net (code "94") (name "DA10-1") (class "Default")
      (node (ref "B13") (pin "E2") (pinfunction "P$2_E2") (pintype "bidirectional"))
      (node (ref "B19") (pin "U2") (pinfunction "E_U2") (pintype "input"))
    )
    (net (code "95") (name "DA11") (class "Default")
      (node (ref "A08") (pin "H2") (pinfunction "P$2_H2") (pintype "bidirectional"))
      (node (ref "A14") (pin "N2") (pinfunction "O$1_N2") (pintype "open_collector"))
    )
    (net (code "96") (name "DA11-0") (class "Default")
      (node (ref "A19") (pin "E2") (pinfunction "I$2_E2") (pintype "input"))
      (node (ref "B08") (pin "H2") (pinfunction "P$2_H2") (pintype "bidirectional"))
    )
    (net (code "97") (name "DA11-1") (class "Default")
      (node (ref "B13") (pin "H2") (pinfunction "P$2_H2") (pintype "bidirectional"))
      (node (ref "B19") (pin "R2") (pinfunction "E_R2") (pintype "input"))
    )
    (net (code "98") (name "DAEX1") (class "Default")
      (node (ref "A11") (pin "D2") (pinfunction "P$2_D2") (pintype "bidirectional"))
      (node (ref "B25") (pin "F2") (pinfunction "O$1_F2") (pintype "open_collector"))
    )
    (net (code "99") (name "DAEX1-0") (class "Default")
      (node (ref "A21") (pin "S2") (pinfunction "I$2_S2") (pintype "input"))
      (node (ref "B11") (pin "D2") (pinfunction "P$2_D2") (pintype "bidirectional"))
    )
    (net (code "100") (name "DAEX1-1") (class "Default")
      (node (ref "B16") (pin "D2") (pinfunction "P$2_D2") (pintype "bidirectional"))
      (node (ref "B20") (pin "U2") (pinfunction "E_U2") (pintype "input"))
    )
    (net (code "101") (name "DAEX2") (class "Default")
      (node (ref "A11") (pin "E2") (pinfunction "P$2_E2") (pintype "bidirectional"))
      (node (ref "B25") (pin "D2") (pinfunction "O$1_D2") (pintype "open_collector"))
    )
    (net (code "102") (name "DAEX2-0") (class "Default")
      (node (ref "A20") (pin "E2") (pinfunction "I$2_E2") (pintype "input"))
      (node (ref "B11") (pin "E2") (pinfunction "P$2_E2") (pintype "bidirectional"))
    )
    (net (code "103") (name "DAEX2-1") (class "Default")
      (node (ref "B16") (pin "E2") (pinfunction "P$2_E2") (pintype "bidirectional"))
      (node (ref "B19") (pin "E2") (pinfunction "E_E2") (pintype "input"))
    )
    (net (code "104") (name "DAEX3") (class "Default")
      (node (ref "A11") (pin "H2") (pinfunction "P$2_H2") (pintype "bidirectional"))
      (node (ref "A14") (pin "T2") (pinfunction "O$1_T2") (pintype "open_collector"))
    )
    (net (code "105") (name "DAEX3-0") (class "Default")
      (node (ref "A20") (pin "L2") (pinfunction "I$2_L2") (pintype "input"))
      (node (ref "B11") (pin "H2") (pinfunction "P$2_H2") (pintype "bidirectional"))
    )
    (net (code "106") (name "DAEX3-1") (class "Default")
      (node (ref "B16") (pin "H2") (pinfunction "P$2_H2") (pintype "bidirectional"))
      (node (ref "B19") (pin "J2") (pinfunction "E_J2") (pintype "input"))
    )
    (net (code "107") (name "DATA_OUT") (class "Default")
      (node (ref "A08") (pin "M2") (pinfunction "P$2_M2") (pintype "bidirectional"))
      (node (ref "B32") (pin "R2") (pinfunction "O$1_R2") (pintype "open_collector"))
    )
    (net (code "108") (name "DATA_OUT0") (class "Default")
      (node (ref "B08") (pin "M2") (pinfunction "P$2_M2") (pintype "bidirectional"))
      (node (ref "B23") (pin "E2") (pinfunction "I$2_E2") (pintype "input"))
    )
    (net (code "109") (name "DATA_OUT1") (class "Default")
      (node (ref "B13") (pin "M2") (pinfunction "P$2_M2") (pintype "bidirectional"))
      (node (ref "B22") (pin "E2") (pinfunction "E_E2") (pintype "input"))
    )
    (net (code "110") (name "DA_SEL_DEV0") (class "Default")
      (node (ref "A16") (pin "D2") (pinfunction "I$1_D2") (pintype "input"))
      (node (ref "A16") (pin "K2") (pinfunction "I$1_K2") (pintype "input"))
      (node (ref "A16") (pin "R2") (pinfunction "I$1_R2") (pintype "input"))
      (node (ref "A17") (pin "D2") (pinfunction "I$1_D2") (pintype "input"))
      (node (ref "A17") (pin "K2") (pinfunction "I$1_K2") (pintype "input"))
      (node (ref "A17") (pin "R2") (pinfunction "I$1_R2") (pintype "input"))
      (node (ref "A18") (pin "D2") (pinfunction "I$1_D2") (pintype "input"))
      (node (ref "A18") (pin "K2") (pinfunction "I$1_K2") (pintype "input"))
      (node (ref "A18") (pin "R2") (pinfunction "I$1_R2") (pintype "input"))
      (node (ref "A19") (pin "D2") (pinfunction "I$1_D2") (pintype "input"))
      (node (ref "A19") (pin "K2") (pinfunction "I$1_K2") (pintype "input"))
      (node (ref "A19") (pin "R2") (pinfunction "I$1_R2") (pintype "input"))
      (node (ref "A20") (pin "D2") (pinfunction "I$1_D2") (pintype "input"))
      (node (ref "A20") (pin "K2") (pinfunction "I$1_K2") (pintype "input"))
      (node (ref "A20") (pin "R2") (pinfunction "I$1_R2") (pintype "input"))
      (node (ref "A21") (pin "R2") (pinfunction "I$1_R2") (pintype "input"))
      (node (ref "A25") (pin "D2") (pinfunction "O$1_D2") (pintype "open_collector"))
      (node (ref "A25") (pin "J2") (pinfunction "O$1_J2") (pintype "open_collector"))
    )
    (net (code "111") (name "DA_SEL_DEV1") (class "Default")
      (node (ref "A25") (pin "F2") (pinfunction "O$1_F2") (pintype "open_collector"))
      (node (ref "A25") (pin "L2") (pinfunction "O$1_L2") (pintype "open_collector"))
      (node (ref "B17") (pin "D2") (pinfunction "D_D2") (pintype "input"))
      (node (ref "B17") (pin "H2") (pinfunction "D_H2") (pintype "input"))
      (node (ref "B17") (pin "L2") (pinfunction "D_L2") (pintype "input"))
      (node (ref "B17") (pin "P2") (pinfunction "D_P2") (pintype "input"))
      (node (ref "B17") (pin "T2") (pinfunction "D_T2") (pintype "input"))
      (node (ref "B18") (pin "D2") (pinfunction "D_D2") (pintype "input"))
      (node (ref "B18") (pin "H2") (pinfunction "D_H2") (pintype "input"))
      (node (ref "B18") (pin "L2") (pinfunction "D_L2") (pintype "input"))
      (node (ref "B18") (pin "P2") (pinfunction "D_P2") (pintype "input"))
      (node (ref "B18") (pin "T2") (pinfunction "D_T2") (pintype "input"))
      (node (ref "B19") (pin "D2") (pinfunction "D_D2") (pintype "input"))
      (node (ref "B19") (pin "H2") (pinfunction "D_H2") (pintype "input"))
      (node (ref "B19") (pin "L2") (pinfunction "D_L2") (pintype "input"))
      (node (ref "B19") (pin "P2") (pinfunction "D_P2") (pintype "input"))
      (node (ref "B19") (pin "T2") (pinfunction "D_T2") (pintype "input"))
      (node (ref "B20") (pin "T2") (pinfunction "D_T2") (pintype "input"))
    )
    (net (code "112") (name "DB0") (class "Default")
      (node (ref "A09") (pin "D2") (pinfunction "P$2_D2") (pintype "bidirectional"))
      (node (ref "B25") (pin "J2") (pinfunction "O$1_J2") (pintype "open_collector"))
    )
    (net (code "113") (name "DB0-0") (class "Default")
      (node (ref "A21") (pin "L2") (pinfunction "I$2_L2") (pintype "input"))
      (node (ref "B09") (pin "D2") (pinfunction "P$2_D2") (pintype "bidirectional"))
    )
    (net (code "114") (name "DB0-1") (class "Default")
      (node (ref "B14") (pin "D2") (pinfunction "P$2_D2") (pintype "bidirectional"))
      (node (ref "B20") (pin "R2") (pinfunction "E_R2") (pintype "input"))
    )
    (net (code "115") (name "DB1") (class "Default")
      (node (ref "A09") (pin "E2") (pinfunction "P$2_E2") (pintype "bidirectional"))
      (node (ref "B25") (pin "L2") (pinfunction "O$1_L2") (pintype "open_collector"))
    )
    (net (code "116") (name "DB1-0") (class "Default")
      (node (ref "A21") (pin "E2") (pinfunction "I$2_E2") (pintype "input"))
      (node (ref "B09") (pin "E2") (pinfunction "P$2_E2") (pintype "bidirectional"))
    )
    (net (code "117") (name "DB1-1") (class "Default")
      (node (ref "B14") (pin "E2") (pinfunction "P$2_E2") (pintype "bidirectional"))
      (node (ref "B20") (pin "M2") (pinfunction "E_M2") (pintype "input"))
    )
    (net (code "118") (name "DB2") (class "Default")
      (node (ref "A09") (pin "H2") (pinfunction "P$2_H2") (pintype "bidirectional"))
      (node (ref "B25") (pin "N2") (pinfunction "O$1_N2") (pintype "open_collector"))
    )
    (net (code "119") (name "DB2-0") (class "Default")
      (node (ref "A22") (pin "S2") (pinfunction "I$2_S2") (pintype "input"))
      (node (ref "B09") (pin "H2") (pinfunction "P$2_H2") (pintype "bidirectional"))
    )
    (net (code "120") (name "DB2-1") (class "Default")
      (node (ref "B14") (pin "H2") (pinfunction "P$2_H2") (pintype "bidirectional"))
      (node (ref "B20") (pin "J2") (pinfunction "E_J2") (pintype "input"))
    )
    (net (code "121") (name "DB3") (class "Default")
      (node (ref "A09") (pin "K2") (pinfunction "P$2_K2") (pintype "bidirectional"))
      (node (ref "B25") (pin "R2") (pinfunction "O$1_R2") (pintype "open_collector"))
    )
    (net (code "122") (name "DB3-0") (class "Default")
      (node (ref "A22") (pin "L2") (pinfunction "I$2_L2") (pintype "input"))
      (node (ref "B09") (pin "K2") (pinfunction "P$2_K2") (pintype "bidirectional"))
    )
    (net (code "123") (name "DB3-1") (class "Default")
      (node (ref "B14") (pin "K2") (pinfunction "P$2_K2") (pintype "bidirectional"))
      (node (ref "B20") (pin "E2") (pinfunction "E_E2") (pintype "input"))
    )
    (net (code "124") (name "DB4") (class "Default")
      (node (ref "A09") (pin "M2") (pinfunction "P$2_M2") (pintype "bidirectional"))
      (node (ref "B25") (pin "T2") (pinfunction "O$1_T2") (pintype "open_collector"))
    )
    (net (code "125") (name "DB4-0") (class "Default")
      (node (ref "A22") (pin "E2") (pinfunction "I$2_E2") (pintype "input"))
      (node (ref "B09") (pin "M2") (pinfunction "P$2_M2") (pintype "bidirectional"))
    )
    (net (code "126") (name "DB4-1") (class "Default")
      (node (ref "B14") (pin "M2") (pinfunction "P$2_M2") (pintype "bidirectional"))
      (node (ref "B21") (pin "U2") (pinfunction "E_U2") (pintype "input"))
    )
    (net (code "127") (name "DB5") (class "Default")
      (node (ref "A09") (pin "P2") (pinfunction "P$2_P2") (pintype "bidirectional"))
      (node (ref "A31") (pin "D2") (pinfunction "O$1_D2") (pintype "open_collector"))
    )
    (net (code "128") (name "DB5-0") (class "Default")
      (node (ref "A23") (pin "S2") (pinfunction "I$2_S2") (pintype "input"))
      (node (ref "B09") (pin "P2") (pinfunction "P$2_P2") (pintype "bidirectional"))
    )
    (net (code "129") (name "DB5-1") (class "Default")
      (node (ref "B14") (pin "P2") (pinfunction "P$2_P2") (pintype "bidirectional"))
      (node (ref "B21") (pin "R2") (pinfunction "E_R2") (pintype "input"))
    )
    (net (code "130") (name "DB6") (class "Default")
      (node (ref "A09") (pin "S2") (pinfunction "P$2_S2") (pintype "bidirectional"))
      (node (ref "A31") (pin "F2") (pinfunction "O$1_F2") (pintype "open_collector"))
    )
    (net (code "131") (name "DB6-0") (class "Default")
      (node (ref "A23") (pin "L2") (pinfunction "I$2_L2") (pintype "input"))
      (node (ref "B09") (pin "S2") (pinfunction "P$2_S2") (pintype "bidirectional"))
    )
    (net (code "132") (name "DB6-1") (class "Default")
      (node (ref "B14") (pin "S2") (pinfunction "P$2_S2") (pintype "bidirectional"))
      (node (ref "B21") (pin "M2") (pinfunction "E_M2") (pintype "input"))
    )
    (net (code "133") (name "DB7") (class "Default")
      (node (ref "A09") (pin "T2") (pinfunction "P$2_T2") (pintype "bidirectional"))
      (node (ref "A31") (pin "J2") (pinfunction "O$1_J2") (pintype "open_collector"))
    )
    (net (code "134") (name "DB7-0") (class "Default")
      (node (ref "A23") (pin "E2") (pinfunction "I$2_E2") (pintype "input"))
      (node (ref "B09") (pin "T2") (pinfunction "P$2_T2") (pintype "bidirectional"))
    )
    (net (code "135") (name "DB7-1") (class "Default")
      (node (ref "B14") (pin "T2") (pinfunction "P$2_T2") (pintype "bidirectional"))
      (node (ref "B21") (pin "J2") (pinfunction "E_J2") (pintype "input"))
    )
    (net (code "136") (name "DB8") (class "Default")
      (node (ref "A09") (pin "V2") (pinfunction "P$2_V2") (pintype "bidirectional"))
      (node (ref "A31") (pin "L2") (pinfunction "O$1_L2") (pintype "open_collector"))
    )
    (net (code "137") (name "DB8-0") (class "Default")
      (node (ref "A24") (pin "S2") (pinfunction "I$2_S2") (pintype "input"))
      (node (ref "B09") (pin "V2") (pinfunction "P$2_V2") (pintype "bidirectional"))
    )
    (net (code "138") (name "DB8-1") (class "Default")
      (node (ref "B14") (pin "V2") (pinfunction "P$2_V2") (pintype "bidirectional"))
      (node (ref "B21") (pin "E2") (pinfunction "E_E2") (pintype "input"))
    )
    (net (code "139") (name "DB9") (class "Default")
      (node (ref "A10") (pin "D2") (pinfunction "P$2_D2") (pintype "bidirectional"))
      (node (ref "A31") (pin "N2") (pinfunction "O$1_N2") (pintype "open_collector"))
    )
    (net (code "140") (name "DB9-0") (class "Default")
      (node (ref "A24") (pin "L2") (pinfunction "I$2_L2") (pintype "input"))
      (node (ref "B10") (pin "D2") (pinfunction "P$2_D2") (pintype "bidirectional"))
    )
    (net (code "141") (name "DB9-1") (class "Default")
      (node (ref "B15") (pin "D2") (pinfunction "P$2_D2") (pintype "bidirectional"))
      (node (ref "B22") (pin "U2") (pinfunction "E_U2") (pintype "input"))
    )
    (net (code "142") (name "DB10") (class "Default")
      (node (ref "A10") (pin "E2") (pinfunction "P$2_E2") (pintype "bidirectional"))
      (node (ref "A31") (pin "R2") (pinfunction "O$1_R2") (pintype "open_collector"))
    )
    (net (code "143") (name "DB10-0") (class "Default")
      (node (ref "A24") (pin "E2") (pinfunction "I$2_E2") (pintype "input"))
      (node (ref "B10") (pin "E2") (pinfunction "P$2_E2") (pintype "bidirectional"))
    )
    (net (code "144") (name "DB10-1") (class "Default")
      (node (ref "B15") (pin "E2") (pinfunction "P$2_E2") (pintype "bidirectional"))
      (node (ref "B22") (pin "R2") (pinfunction "E_R2") (pintype "input"))
    )
    (net (code "145") (name "DB11") (class "Default")
      (node (ref "A10") (pin "H2") (pinfunction "P$2_H2") (pintype "bidirectional"))
      (node (ref "A31") (pin "T2") (pinfunction "O$1_T2") (pintype "open_collector"))
    )
    (net (code "146") (name "DB11-0") (class "Default")
      (node (ref "B10") (pin "H2") (pinfunction "P$2_H2") (pintype "bidirectional"))
      (node (ref "B23") (pin "S2") (pinfunction "I$2_S2") (pintype "input"))
    )
    (net (code "147") (name "DB11-1") (class "Default")
      (node (ref "B15") (pin "H2") (pinfunction "P$2_H2") (pintype "bidirectional"))
      (node (ref "B22") (pin "M2") (pinfunction "E_M2") (pintype "input"))
    )
    (net (code "148") (name "DB_SEL_DEV0") (class "Default")
      (node (ref "A12") (pin "D2") (pinfunction "O$1_D2") (pintype "open_collector"))
      (node (ref "A12") (pin "N2") (pinfunction "O$1_N2") (pintype "open_collector"))
      (node (ref "A21") (pin "D2") (pinfunction "I$1_D2") (pintype "input"))
      (node (ref "A21") (pin "K2") (pinfunction "I$1_K2") (pintype "input"))
      (node (ref "A22") (pin "D2") (pinfunction "I$1_D2") (pintype "input"))
      (node (ref "A22") (pin "K2") (pinfunction "I$1_K2") (pintype "input"))
      (node (ref "A22") (pin "R2") (pinfunction "I$1_R2") (pintype "input"))
      (node (ref "A23") (pin "D2") (pinfunction "I$1_D2") (pintype "input"))
      (node (ref "A23") (pin "K2") (pinfunction "I$1_K2") (pintype "input"))
      (node (ref "A23") (pin "R2") (pinfunction "I$1_R2") (pintype "input"))
      (node (ref "A24") (pin "D2") (pinfunction "I$1_D2") (pintype "input"))
      (node (ref "A24") (pin "K2") (pinfunction "I$1_K2") (pintype "input"))
      (node (ref "A24") (pin "R2") (pinfunction "I$1_R2") (pintype "input"))
      (node (ref "B23") (pin "D2") (pinfunction "I$1_D2") (pintype "input"))
      (node (ref "B23") (pin "K2") (pinfunction "I$1_K2") (pintype "input"))
      (node (ref "B23") (pin "R2") (pinfunction "I$1_R2") (pintype "input"))
    )
    (net (code "149") (name "DB_SEL_DEV1") (class "Default")
      (node (ref "A12") (pin "F2") (pinfunction "O$1_F2") (pintype "open_collector"))
      (node (ref "A12") (pin "R2") (pinfunction "O$1_R2") (pintype "open_collector"))
      (node (ref "B20") (pin "D2") (pinfunction "D_D2") (pintype "input"))
      (node (ref "B20") (pin "H2") (pinfunction "D_H2") (pintype "input"))
      (node (ref "B20") (pin "L2") (pinfunction "D_L2") (pintype "input"))
      (node (ref "B20") (pin "P2") (pinfunction "D_P2") (pintype "input"))
      (node (ref "B21") (pin "D2") (pinfunction "D_D2") (pintype "input"))
      (node (ref "B21") (pin "H2") (pinfunction "D_H2") (pintype "input"))
      (node (ref "B21") (pin "L2") (pinfunction "D_L2") (pintype "input"))
      (node (ref "B21") (pin "P2") (pinfunction "D_P2") (pintype "input"))
      (node (ref "B21") (pin "T2") (pinfunction "D_T2") (pintype "input"))
      (node (ref "B22") (pin "D2") (pinfunction "D_D2") (pintype "input"))
      (node (ref "B22") (pin "H2") (pinfunction "D_H2") (pintype "input"))
      (node (ref "B22") (pin "L2") (pinfunction "D_L2") (pintype "input"))
      (node (ref "B22") (pin "P2") (pinfunction "D_P2") (pintype "input"))
      (node (ref "B22") (pin "T2") (pinfunction "D_T2") (pintype "input"))
    )
    (net (code "150") (name "DF0") (class "Default")
      (node (ref "A11") (pin "K2") (pinfunction "P$2_K2") (pintype "bidirectional"))
      (node (ref "B11") (pin "K2") (pinfunction "P$2_K2") (pintype "bidirectional"))
      (node (ref "B16") (pin "K2") (pinfunction "P$2_K2") (pintype "bidirectional"))
    )
    (net (code "151") (name "DF1") (class "Default")
      (node (ref "A11") (pin "M2") (pinfunction "P$2_M2") (pintype "bidirectional"))
      (node (ref "B11") (pin "M2") (pinfunction "P$2_M2") (pintype "bidirectional"))
      (node (ref "B16") (pin "M2") (pinfunction "P$2_M2") (pintype "bidirectional"))
    )
    (net (code "152") (name "DF2") (class "Default")
      (node (ref "A11") (pin "P2") (pinfunction "P$2_P2") (pintype "bidirectional"))
      (node (ref "B11") (pin "P2") (pinfunction "P$2_P2") (pintype "bidirectional"))
      (node (ref "B16") (pin "P2") (pinfunction "P$2_P2") (pintype "bidirectional"))
    )
    (net (code "153") (name "GND") (class "Default")
      (node (ref "A28") (pin "E2") (pinfunction "EN0_E2") (pintype "input"))
      (node (ref "B26") (pin "H2") (pinfunction "G_H2") (pintype "input"))
      (node (ref "B26") (pin "N2") (pinfunction "G_N2") (pintype "input"))
      (node (ref "B26") (pin "U2") (pinfunction "G_U2") (pintype "input"))
      (node (ref "B28") (pin "J2") (pinfunction "J_J2") (pintype "input"))
      (node (ref "B28") (pin "P2") (pinfunction "J_P2") (pintype "input"))
      (node (ref "B28") (pin "V2") (pinfunction "J_V2") (pintype "input"))
      (node (ref "B29") (pin "F2") (pinfunction "F_F2") (pintype "input"))
      (node (ref "B29") (pin "P2") (pinfunction "F_P2") (pintype "input"))
    )
    (net (code "154") (name "INC_MB") (class "Default")
      (node (ref "A08") (pin "T2") (pinfunction "P$2_T2") (pintype "bidirectional"))
      (node (ref "B08") (pin "T2") (pinfunction "P$2_T2") (pintype "bidirectional"))
      (node (ref "B13") (pin "T2") (pinfunction "P$2_T2") (pintype "bidirectional"))
    )
    (net (code "155") (name "IOP1") (class "Default")
      (node (ref "A02") (pin "K2") (pinfunction "P$2_K2") (pintype "bidirectional"))
      (node (ref "B02") (pin "K2") (pinfunction "P$2_K2") (pintype "bidirectional"))
    )
    (net (code "156") (name "IOP2") (class "Default")
      (node (ref "A02") (pin "M2") (pinfunction "P$2_M2") (pintype "bidirectional"))
      (node (ref "B02") (pin "M2") (pinfunction "P$2_M2") (pintype "bidirectional"))
    )
    (net (code "157") (name "IOP4") (class "Default")
      (node (ref "A02") (pin "P2") (pinfunction "P$2_P2") (pintype "bidirectional"))
      (node (ref "B02") (pin "P2") (pinfunction "P$2_P2") (pintype "bidirectional"))
    )
    (net (code "158") (name "MPX0") (class "Default")
      (node (ref "A25") (pin "E2") (pinfunction "I$1_E2") (pintype "input"))
      (node (ref "A25") (pin "K2") (pinfunction "I$1_K2") (pintype "input"))
      (node (ref "A30") (pin "S2") (pinfunction "P$2_S2") (pintype "bidirectional"))
      (node (ref "A32") (pin "M2") (pinfunction "M_M2") (pintype "input"))
      (node (ref "B27") (pin "J2") (pinfunction "1_J2") (pintype "open_collector"))
      (node (ref "B27") (pin "P2") (pinfunction "EN0_P2") (pintype "input"))
      (node (ref "B30") (pin "D2") (pinfunction "I$1_D2") (pintype "input"))
    )
    (net (code "159") (name "MPX1") (class "Default")
      (node (ref "A12") (pin "T2") (pinfunction "O$1_T2") (pintype "open_collector"))
      (node (ref "A25") (pin "H2") (pinfunction "I$1_H2") (pintype "input"))
      (node (ref "A25") (pin "M2") (pinfunction "I$1_M2") (pintype "input"))
      (node (ref "A30") (pin "P2") (pinfunction "P$2_P2") (pintype "bidirectional"))
      (node (ref "A32") (pin "F2") (pinfunction "F_F2") (pintype "input"))
      (node (ref "B30") (pin "K2") (pinfunction "I$1_K2") (pintype "input"))
      (node (ref "B31") (pin "J2") (pinfunction "1_J2") (pintype "open_collector"))
      (node (ref "B31") (pin "P2") (pinfunction "EN0_P2") (pintype "input"))
    )
    (net (code "160") (name "Net-(A12E-O$1)") (class "Default")
      (node (ref "A12") (pin "J2") (pinfunction "O$1_J2") (pintype "open_collector"))
      (node (ref "B27") (pin "E2") (pinfunction "EN0_E2") (pintype "input"))
    )
    (net (code "161") (name "Net-(A12F-O$1)") (class "Default")
      (node (ref "A12") (pin "L2") (pinfunction "O$1_L2") (pintype "open_collector"))
      (node (ref "B31") (pin "E2") (pinfunction "EN0_E2") (pintype "input"))
    )
    (net (code "162") (name "Net-(A12I-I$1)") (class "Default")
      (node (ref "A12") (pin "U2") (pinfunction "I$1_U2") (pintype "input"))
      (node (ref "A32") (pin "S2") (pinfunction "S_S2") (pintype "output"))
    )
    (net (code "163") (name "Net-(A13A-I$1)") (class "Default")
      (node (ref "A13") (pin "E2") (pinfunction "I$1_E2") (pintype "input"))
      (node (ref "A15") (pin "D2") (pinfunction "P$1_D2") (pintype "passive"))
      (node (ref "A16") (pin "U2") (pinfunction "O$1_U2") (pintype "open_collector"))
    )
    (net (code "164") (name "Net-(A13B-I$1)") (class "Default")
      (node (ref "A13") (pin "H2") (pinfunction "I$1_H2") (pintype "input"))
      (node (ref "A15") (pin "E2") (pinfunction "P$1_E2") (pintype "passive"))
      (node (ref "A16") (pin "N2") (pinfunction "O$1_N2") (pintype "open_collector"))
    )
    (net (code "165") (name "Net-(A13E-I$1)") (class "Default")
      (node (ref "A13") (pin "K2") (pinfunction "I$1_K2") (pintype "input"))
      (node (ref "A15") (pin "F2") (pinfunction "P$1_F2") (pintype "passive"))
      (node (ref "A16") (pin "H2") (pinfunction "O$1_H2") (pintype "open_collector"))
    )
    (net (code "166") (name "Net-(A13F-I$1)") (class "Default")
      (node (ref "A13") (pin "M2") (pinfunction "I$1_M2") (pintype "input"))
      (node (ref "A15") (pin "H2") (pinfunction "P$1_H2") (pintype "passive"))
      (node (ref "A17") (pin "U2") (pinfunction "O$1_U2") (pintype "open_collector"))
    )
    (net (code "167") (name "Net-(A13G-I$1)") (class "Default")
      (node (ref "A13") (pin "P2") (pinfunction "I$1_P2") (pintype "input"))
      (node (ref "A15") (pin "J2") (pinfunction "P$1_J2") (pintype "passive"))
      (node (ref "A17") (pin "N2") (pinfunction "O$1_N2") (pintype "open_collector"))
    )
    (net (code "168") (name "Net-(A13H-I$1)") (class "Default")
      (node (ref "A13") (pin "S2") (pinfunction "I$1_S2") (pintype "input"))
      (node (ref "A15") (pin "K2") (pinfunction "P$1_K2") (pintype "passive"))
      (node (ref "A17") (pin "H2") (pinfunction "O$1_H2") (pintype "open_collector"))
    )
    (net (code "169") (name "Net-(A13I-I$1)") (class "Default")
      (node (ref "A13") (pin "U2") (pinfunction "I$1_U2") (pintype "input"))
      (node (ref "A15") (pin "L2") (pinfunction "P$1_L2") (pintype "passive"))
      (node (ref "A18") (pin "U2") (pinfunction "O$1_U2") (pintype "open_collector"))
    )
    (net (code "170") (name "Net-(A14A-I$1)") (class "Default")
      (node (ref "A14") (pin "E2") (pinfunction "I$1_E2") (pintype "input"))
      (node (ref "A15") (pin "M2") (pinfunction "P$1_M2") (pintype "passive"))
      (node (ref "A18") (pin "N2") (pinfunction "O$1_N2") (pintype "open_collector"))
    )
    (net (code "171") (name "Net-(A14B-I$1)") (class "Default")
      (node (ref "A14") (pin "H2") (pinfunction "I$1_H2") (pintype "input"))
      (node (ref "A15") (pin "N2") (pinfunction "P$1_N2") (pintype "passive"))
      (node (ref "A18") (pin "H2") (pinfunction "O$1_H2") (pintype "open_collector"))
    )
    (net (code "172") (name "Net-(A14E-I$1)") (class "Default")
      (node (ref "A14") (pin "K2") (pinfunction "I$1_K2") (pintype "input"))
      (node (ref "A15") (pin "P2") (pinfunction "P$1_P2") (pintype "passive"))
      (node (ref "A19") (pin "U2") (pinfunction "O$1_U2") (pintype "open_collector"))
    )
    (net (code "173") (name "Net-(A14F-I$1)") (class "Default")
      (node (ref "A14") (pin "M2") (pinfunction "I$1_M2") (pintype "input"))
      (node (ref "A15") (pin "R2") (pinfunction "P$1_R2") (pintype "passive"))
      (node (ref "A19") (pin "N2") (pinfunction "O$1_N2") (pintype "open_collector"))
    )
    (net (code "174") (name "Net-(A14G-I$1)") (class "Default")
      (node (ref "A14") (pin "P2") (pinfunction "I$1_P2") (pintype "input"))
      (node (ref "A15") (pin "S2") (pinfunction "P$1_S2") (pintype "passive"))
      (node (ref "A19") (pin "H2") (pinfunction "O$1_H2") (pintype "open_collector"))
    )
    (net (code "175") (name "Net-(A14H-I$1)") (class "Default")
      (node (ref "A14") (pin "S2") (pinfunction "I$1_S2") (pintype "input"))
      (node (ref "A15") (pin "T2") (pinfunction "P$1_T2") (pintype "passive"))
      (node (ref "A20") (pin "U2") (pinfunction "O$1_U2") (pintype "open_collector"))
    )
    (net (code "176") (name "Net-(A14I-I$1)") (class "Default")
      (node (ref "A14") (pin "U2") (pinfunction "I$1_U2") (pintype "input"))
      (node (ref "A15") (pin "U2") (pinfunction "P$1_U2") (pintype "passive"))
      (node (ref "A20") (pin "N2") (pinfunction "O$1_N2") (pintype "open_collector"))
    )
    (net (code "177") (name "Net-(A15Q-P$1)") (class "Default")
      (node (ref "A15") (pin "V2") (pinfunction "P$1_V2") (pintype "passive"))
      (node (ref "A20") (pin "H2") (pinfunction "O$1_H2") (pintype "open_collector"))
      (node (ref "B25") (pin "E2") (pinfunction "I$1_E2") (pintype "input"))
    )
    (net (code "178") (name "Net-(A16C-I$3)") (class "Default")
      (node (ref "A16") (pin "F2") (pinfunction "I$3_F2") (pintype "passive"))
      (node (ref "B17") (pin "N2") (pinfunction "F_N2") (pintype "open_collector"))
    )
    (net (code "179") (name "Net-(A16E-I$3)") (class "Default")
      (node (ref "A16") (pin "M2") (pinfunction "I$3_M2") (pintype "passive"))
      (node (ref "B17") (pin "S2") (pinfunction "F_S2") (pintype "open_collector"))
    )
    (net (code "180") (name "Net-(A16G-I$3)") (class "Default")
      (node (ref "A16") (pin "T2") (pinfunction "I$3_T2") (pintype "passive"))
      (node (ref "B17") (pin "V2") (pinfunction "F_V2") (pintype "open_collector"))
    )
    (net (code "181") (name "Net-(A17C-I$3)") (class "Default")
      (node (ref "A17") (pin "F2") (pinfunction "I$3_F2") (pintype "passive"))
      (node (ref "B18") (pin "V2") (pinfunction "F_V2") (pintype "open_collector"))
    )
    (net (code "182") (name "Net-(A17E-I$3)") (class "Default")
      (node (ref "A17") (pin "M2") (pinfunction "I$3_M2") (pintype "passive"))
      (node (ref "B17") (pin "F2") (pinfunction "F_F2") (pintype "open_collector"))
    )
    (net (code "183") (name "Net-(A17G-I$3)") (class "Default")
      (node (ref "A17") (pin "T2") (pinfunction "I$3_T2") (pintype "passive"))
      (node (ref "B17") (pin "K2") (pinfunction "F_K2") (pintype "open_collector"))
    )
    (net (code "184") (name "Net-(A18C-I$3)") (class "Default")
      (node (ref "A18") (pin "F2") (pinfunction "I$3_F2") (pintype "passive"))
      (node (ref "B18") (pin "K2") (pinfunction "F_K2") (pintype "open_collector"))
    )
    (net (code "185") (name "Net-(A18E-I$3)") (class "Default")
      (node (ref "A18") (pin "M2") (pinfunction "I$3_M2") (pintype "passive"))
      (node (ref "B18") (pin "N2") (pinfunction "F_N2") (pintype "open_collector"))
    )
    (net (code "186") (name "Net-(A18G-I$3)") (class "Default")
      (node (ref "A18") (pin "T2") (pinfunction "I$3_T2") (pintype "passive"))
      (node (ref "B18") (pin "S2") (pinfunction "F_S2") (pintype "open_collector"))
    )
    (net (code "187") (name "Net-(A19C-I$3)") (class "Default")
      (node (ref "A19") (pin "F2") (pinfunction "I$3_F2") (pintype "passive"))
      (node (ref "B19") (pin "S2") (pinfunction "F_S2") (pintype "open_collector"))
    )
    (net (code "188") (name "Net-(A19E-I$3)") (class "Default")
      (node (ref "A19") (pin "M2") (pinfunction "I$3_M2") (pintype "passive"))
      (node (ref "B19") (pin "V2") (pinfunction "F_V2") (pintype "open_collector"))
    )
    (net (code "189") (name "Net-(A19G-I$3)") (class "Default")
      (node (ref "A19") (pin "T2") (pinfunction "I$3_T2") (pintype "passive"))
      (node (ref "B18") (pin "F2") (pinfunction "F_F2") (pintype "open_collector"))
    )
    (net (code "190") (name "Net-(A20C-I$3)") (class "Default")
      (node (ref "A20") (pin "F2") (pinfunction "I$3_F2") (pintype "passive"))
      (node (ref "B19") (pin "F2") (pinfunction "F_F2") (pintype "open_collector"))
    )
    (net (code "191") (name "Net-(A20E-I$3)") (class "Default")
      (node (ref "A20") (pin "M2") (pinfunction "I$3_M2") (pintype "passive"))
      (node (ref "B19") (pin "K2") (pinfunction "F_K2") (pintype "open_collector"))
    )
    (net (code "192") (name "Net-(A20G-I$3)") (class "Default")
      (node (ref "A20") (pin "T2") (pinfunction "I$3_T2") (pintype "passive"))
      (node (ref "B19") (pin "N2") (pinfunction "F_N2") (pintype "open_collector"))
    )
    (net (code "193") (name "Net-(A21C-I$3)") (class "Default")
      (node (ref "A21") (pin "F2") (pinfunction "I$3_F2") (pintype "passive"))
      (node (ref "B20") (pin "N2") (pinfunction "F_N2") (pintype "open_collector"))
    )
    (net (code "194") (name "Net-(A21C-O$1)") (class "Default")
      (node (ref "A21") (pin "H2") (pinfunction "O$1_H2") (pintype "open_collector"))
      (node (ref "B24") (pin "F2") (pinfunction "P$1_F2") (pintype "passive"))
      (node (ref "B25") (pin "M2") (pinfunction "I$1_M2") (pintype "input"))
    )
    (net (code "195") (name "Net-(A21E-I$3)") (class "Default")
      (node (ref "A21") (pin "M2") (pinfunction "I$3_M2") (pintype "passive"))
      (node (ref "B20") (pin "S2") (pinfunction "F_S2") (pintype "open_collector"))
    )
    (net (code "196") (name "Net-(A21E-O$1)") (class "Default")
      (node (ref "A21") (pin "N2") (pinfunction "O$1_N2") (pintype "open_collector"))
      (node (ref "B24") (pin "E2") (pinfunction "P$1_E2") (pintype "passive"))
      (node (ref "B25") (pin "K2") (pinfunction "I$1_K2") (pintype "input"))
    )
    (net (code "197") (name "Net-(A21G-I$3)") (class "Default")
      (node (ref "A21") (pin "T2") (pinfunction "I$3_T2") (pintype "passive"))
      (node (ref "B20") (pin "V2") (pinfunction "F_V2") (pintype "open_collector"))
    )
    (net (code "198") (name "Net-(A21G-O$1)") (class "Default")
      (node (ref "A21") (pin "U2") (pinfunction "O$1_U2") (pintype "open_collector"))
      (node (ref "B24") (pin "D2") (pinfunction "P$1_D2") (pintype "passive"))
      (node (ref "B25") (pin "H2") (pinfunction "I$1_H2") (pintype "input"))
    )
    (net (code "199") (name "Net-(A22C-I$3)") (class "Default")
      (node (ref "A22") (pin "F2") (pinfunction "I$3_F2") (pintype "passive"))
      (node (ref "B21") (pin "V2") (pinfunction "F_V2") (pintype "open_collector"))
    )
    (net (code "200") (name "Net-(A22C-O$1)") (class "Default")
      (node (ref "A22") (pin "H2") (pinfunction "O$1_H2") (pintype "open_collector"))
      (node (ref "B24") (pin "K2") (pinfunction "P$1_K2") (pintype "passive"))
      (node (ref "B25") (pin "U2") (pinfunction "I$1_U2") (pintype "input"))
    )
    (net (code "201") (name "Net-(A22E-I$3)") (class "Default")
      (node (ref "A22") (pin "M2") (pinfunction "I$3_M2") (pintype "passive"))
      (node (ref "B20") (pin "F2") (pinfunction "F_F2") (pintype "open_collector"))
    )
    (net (code "202") (name "Net-(A22E-O$1)") (class "Default")
      (node (ref "A22") (pin "N2") (pinfunction "O$1_N2") (pintype "open_collector"))
      (node (ref "B24") (pin "J2") (pinfunction "P$1_J2") (pintype "passive"))
      (node (ref "B25") (pin "S2") (pinfunction "I$1_S2") (pintype "input"))
    )
    (net (code "203") (name "Net-(A22G-I$3)") (class "Default")
      (node (ref "A22") (pin "T2") (pinfunction "I$3_T2") (pintype "passive"))
      (node (ref "B20") (pin "K2") (pinfunction "F_K2") (pintype "open_collector"))
    )
    (net (code "204") (name "Net-(A22G-O$1)") (class "Default")
      (node (ref "A22") (pin "U2") (pinfunction "O$1_U2") (pintype "open_collector"))
      (node (ref "B24") (pin "H2") (pinfunction "P$1_H2") (pintype "passive"))
      (node (ref "B25") (pin "P2") (pinfunction "I$1_P2") (pintype "input"))
    )
    (net (code "205") (name "Net-(A23C-I$3)") (class "Default")
      (node (ref "A23") (pin "F2") (pinfunction "I$3_F2") (pintype "passive"))
      (node (ref "B21") (pin "K2") (pinfunction "F_K2") (pintype "open_collector"))
    )
    (net (code "206") (name "Net-(A23C-O$1)") (class "Default")
      (node (ref "A23") (pin "H2") (pinfunction "O$1_H2") (pintype "open_collector"))
      (node (ref "A31") (pin "K2") (pinfunction "I$1_K2") (pintype "input"))
      (node (ref "B24") (pin "N2") (pinfunction "P$1_N2") (pintype "passive"))
    )
    (net (code "207") (name "Net-(A23E-I$3)") (class "Default")
      (node (ref "A23") (pin "M2") (pinfunction "I$3_M2") (pintype "passive"))
      (node (ref "B21") (pin "N2") (pinfunction "F_N2") (pintype "open_collector"))
    )
    (net (code "208") (name "Net-(A23E-O$1)") (class "Default")
      (node (ref "A23") (pin "N2") (pinfunction "O$1_N2") (pintype "open_collector"))
      (node (ref "A31") (pin "H2") (pinfunction "I$1_H2") (pintype "input"))
      (node (ref "B24") (pin "M2") (pinfunction "P$1_M2") (pintype "passive"))
    )
    (net (code "209") (name "Net-(A23G-I$3)") (class "Default")
      (node (ref "A23") (pin "T2") (pinfunction "I$3_T2") (pintype "passive"))
      (node (ref "B21") (pin "S2") (pinfunction "F_S2") (pintype "open_collector"))
    )
    (net (code "210") (name "Net-(A23G-O$1)") (class "Default")
      (node (ref "A23") (pin "U2") (pinfunction "O$1_U2") (pintype "open_collector"))
      (node (ref "A31") (pin "E2") (pinfunction "I$1_E2") (pintype "input"))
      (node (ref "B24") (pin "L2") (pinfunction "P$1_L2") (pintype "passive"))
    )
    (net (code "211") (name "Net-(A24C-I$3)") (class "Default")
      (node (ref "A24") (pin "F2") (pinfunction "I$3_F2") (pintype "passive"))
      (node (ref "B22") (pin "S2") (pinfunction "F_S2") (pintype "open_collector"))
    )
    (net (code "212") (name "Net-(A24C-O$1)") (class "Default")
      (node (ref "A24") (pin "H2") (pinfunction "O$1_H2") (pintype "open_collector"))
      (node (ref "A31") (pin "S2") (pinfunction "I$1_S2") (pintype "input"))
      (node (ref "B24") (pin "S2") (pinfunction "P$1_S2") (pintype "passive"))
    )
    (net (code "213") (name "Net-(A24E-I$3)") (class "Default")
      (node (ref "A24") (pin "M2") (pinfunction "I$3_M2") (pintype "passive"))
      (node (ref "B22") (pin "V2") (pinfunction "F_V2") (pintype "open_collector"))
    )
    (net (code "214") (name "Net-(A24E-O$1)") (class "Default")
      (node (ref "A24") (pin "N2") (pinfunction "O$1_N2") (pintype "open_collector"))
      (node (ref "A31") (pin "P2") (pinfunction "I$1_P2") (pintype "input"))
      (node (ref "B24") (pin "R2") (pinfunction "P$1_R2") (pintype "passive"))
    )
    (net (code "215") (name "Net-(A24G-I$3)") (class "Default")
      (node (ref "A24") (pin "T2") (pinfunction "I$3_T2") (pintype "passive"))
      (node (ref "B21") (pin "F2") (pinfunction "F_F2") (pintype "open_collector"))
    )
    (net (code "216") (name "Net-(A24G-O$1)") (class "Default")
      (node (ref "A24") (pin "U2") (pinfunction "O$1_U2") (pintype "open_collector"))
      (node (ref "A31") (pin "M2") (pinfunction "I$1_M2") (pintype "input"))
      (node (ref "B24") (pin "P2") (pinfunction "P$1_P2") (pintype "passive"))
    )
    (net (code "217") (name "Net-(A25G-I$1)") (class "Default")
      (node (ref "A25") (pin "P2") (pinfunction "I$1_P2") (pintype "input"))
      (node (ref "A26") (pin "H2") (pinfunction "O$1_H2") (pintype "open_collector"))
      (node (ref "A26") (pin "J2") (pinfunction "P$1_J2") (pintype "passive"))
    )
    (net (code "218") (name "Net-(A25H-I$1)") (class "Default")
      (node (ref "A25") (pin "S2") (pinfunction "I$1_S2") (pintype "input"))
      (node (ref "A26") (pin "N2") (pinfunction "O$1_N2") (pintype "open_collector"))
      (node (ref "A26") (pin "P2") (pinfunction "P$1_P2") (pintype "passive"))
    )
    (net (code "219") (name "Net-(A26G-O$1)") (class "Default")
      (node (ref "A26") (pin "U2") (pinfunction "O$1_U2") (pintype "open_collector"))
      (node (ref "A26") (pin "V2") (pinfunction "P$1_V2") (pintype "passive"))
      (node (ref "B32") (pin "E2") (pinfunction "I$1_E2") (pintype "input"))
    )
    (net (code "220") (name "Net-(A27C-O$1)") (class "Default")
      (node (ref "A27") (pin "H2") (pinfunction "O$1_H2") (pintype "open_collector"))
      (node (ref "A27") (pin "J2") (pinfunction "P$1_J2") (pintype "passive"))
      (node (ref "B28") (pin "R2") (pinfunction "D_R2") (pintype "input"))
    )
    (net (code "221") (name "Net-(A27E-O$1)") (class "Default")
      (node (ref "A27") (pin "N2") (pinfunction "O$1_N2") (pintype "open_collector"))
      (node (ref "A27") (pin "P2") (pinfunction "P$1_P2") (pintype "passive"))
      (node (ref "B29") (pin "N2") (pinfunction "E_N2") (pintype "input"))
    )
    (net (code "222") (name "Net-(A28C-PU1)") (class "Default")
      (node (ref "A28") (pin "K2") (pinfunction "PU1_K2") (pintype "input"))
      (node (ref "B26") (pin "F2") (pinfunction "O_F2") (pintype "open_collector"))
      (node (ref "B27") (pin "N2") (pinfunction "PU0_N2") (pintype "input"))
      (node (ref "B27") (pin "U2") (pinfunction "PU1_U2") (pintype "input"))
      (node (ref "B31") (pin "N2") (pinfunction "PU0_N2") (pintype "input"))
      (node (ref "B31") (pin "U2") (pinfunction "PU1_U2") (pintype "input"))
    )
    (net (code "223") (name "Net-(A28C-RESET)") (class "Default")
      (node (ref "A28") (pin "F2") (pinfunction "RESET_F2") (pintype "input"))
      (node (ref "B27") (pin "F2") (pinfunction "RESET_F2") (pintype "input"))
      (node (ref "B27") (pin "R2") (pinfunction "RESET_R2") (pintype "input"))
      (node (ref "B31") (pin "F2") (pinfunction "RESET_F2") (pintype "input"))
      (node (ref "B31") (pin "R2") (pinfunction "RESET_R2") (pintype "input"))
      (node (ref "B32") (pin "J2") (pinfunction "O$1_J2") (pintype "open_collector"))
    )
    (net (code "224") (name "Net-(A31I-I$1)") (class "Default")
      (node (ref "A31") (pin "U2") (pinfunction "I$1_U2") (pintype "input"))
      (node (ref "B23") (pin "U2") (pinfunction "O$1_U2") (pintype "open_collector"))
      (node (ref "B24") (pin "T2") (pinfunction "P$1_T2") (pintype "passive"))
    )
    (net (code "225") (name "Net-(B22A-F)") (class "Default")
      (node (ref "B22") (pin "F2") (pinfunction "F_F2") (pintype "open_collector"))
      (node (ref "B23") (pin "F2") (pinfunction "I$3_F2") (pintype "passive"))
    )
    (net (code "226") (name "Net-(B22D-F)") (class "Default")
      (node (ref "B22") (pin "K2") (pinfunction "F_K2") (pintype "open_collector"))
      (node (ref "B23") (pin "M2") (pinfunction "I$3_M2") (pintype "passive"))
    )
    (net (code "227") (name "Net-(B22E-F)") (class "Default")
      (node (ref "B22") (pin "N2") (pinfunction "F_N2") (pintype "open_collector"))
      (node (ref "B23") (pin "T2") (pinfunction "I$3_T2") (pintype "passive"))
    )
    (net (code "228") (name "Net-(B23C-O$1)") (class "Default")
      (node (ref "B23") (pin "H2") (pinfunction "O$1_H2") (pintype "open_collector"))
      (node (ref "B24") (pin "V2") (pinfunction "P$1_V2") (pintype "passive"))
      (node (ref "B32") (pin "S2") (pinfunction "I$1_S2") (pintype "input"))
    )
    (net (code "229") (name "Net-(B23E-O$1)") (class "Default")
      (node (ref "B23") (pin "N2") (pinfunction "O$1_N2") (pintype "open_collector"))
      (node (ref "B24") (pin "U2") (pinfunction "P$1_U2") (pintype "passive"))
      (node (ref "B32") (pin "P2") (pinfunction "I$1_P2") (pintype "input"))
    )
    (net (code "230") (name "Net-(B26A-I$1)") (class "Default")
      (node (ref "B26") (pin "J2") (pinfunction "I$1_J2") (pintype "passive"))
      (node (ref "B32") (pin "F2") (pinfunction "O$1_F2") (pintype "open_collector"))
    )
    (net (code "231") (name "Net-(B26D-O)") (class "Default")
      (node (ref "B26") (pin "M2") (pinfunction "O_M2") (pintype "open_collector"))
      (node (ref "B27") (pin "K2") (pinfunction "PU1_K2") (pintype "input"))
      (node (ref "B31") (pin "K2") (pinfunction "PU1_K2") (pintype "input"))
    )
    (net (code "232") (name "Net-(B26D-PU0)") (class "Default")
      (node (ref "B26") (pin "K2") (pinfunction "PU0_K2") (pintype "input"))
      (node (ref "B26") (pin "R2") (pinfunction "PU0_R2") (pintype "input"))
      (node (ref "B29") (pin "M2") (pinfunction "M_M2") (pintype "output"))
    )
    (net (code "233") (name "Net-(B26E-O)") (class "Default")
      (node (ref "B26") (pin "T2") (pinfunction "O_T2") (pintype "open_collector"))
      (node (ref "B27") (pin "D2") (pinfunction "PU0_D2") (pintype "input"))
      (node (ref "B31") (pin "D2") (pinfunction "PU0_D2") (pintype "input"))
    )
    (net (code "234") (name "Net-(B27C-0)") (class "Default")
      (node (ref "B27") (pin "H2") (pinfunction "0_H2") (pintype "open_collector"))
      (node (ref "B27") (pin "V2") (pinfunction "EN1_V2") (pintype "input"))
    )
    (net (code "235") (name "Net-(B28A-D)") (class "Default")
      (node (ref "B28") (pin "D2") (pinfunction "D_D2") (pintype "input"))
      (node (ref "B30") (pin "H2") (pinfunction "O$1_H2") (pintype "open_collector"))
      (node (ref "B30") (pin "J2") (pinfunction "P$1_J2") (pintype "passive"))
    )
    (net (code "236") (name "Net-(B28B-D)") (class "Default")
      (node (ref "B28") (pin "K2") (pinfunction "D_K2") (pintype "input"))
      (node (ref "B30") (pin "N2") (pinfunction "O$1_N2") (pintype "open_collector"))
      (node (ref "B30") (pin "P2") (pinfunction "P$1_P2") (pintype "passive"))
    )
    (net (code "237") (name "Net-(B29C-E)") (class "Default")
      (node (ref "B29") (pin "E2") (pinfunction "E_E2") (pintype "input"))
      (node (ref "B32") (pin "L2") (pinfunction "O$1_L2") (pintype "open_collector"))
    )
    (net (code "238") (name "Net-(B29C-J)") (class "Default")
      (node (ref "B29") (pin "J2") (pinfunction "J_J2") (pintype "passive"))
      (node (ref "B29") (pin "K2") (pinfunction "K_K2") (pintype "passive"))
    )
    (net (code "239") (name "Net-(B29D-J)") (class "Default")
      (node (ref "B29") (pin "S2") (pinfunction "J_S2") (pintype "passive"))
      (node (ref "B29") (pin "T2") (pinfunction "K_T2") (pintype "passive"))
    )
    (net (code "240") (name "Net-(B31C-0)") (class "Default")
      (node (ref "B31") (pin "H2") (pinfunction "0_H2") (pintype "open_collector"))
      (node (ref "B31") (pin "V2") (pinfunction "EN1_V2") (pintype "input"))
    )
    (net (code "241") (name "Net-(B32I-O$1)") (class "Default")
      (node (ref "B32") (pin "T2") (pinfunction "O$1_T2") (pintype "open_collector"))
      (node (ref "PDP-8I") (pin "2") (pinfunction "2_2") (pintype "passive"))
    )
    (net (code "242") (name "POWER_CLEAR") (class "Default")
      (node (ref "A02") (pin "V2") (pinfunction "P$2_V2") (pintype "bidirectional"))
      (node (ref "B02") (pin "V2") (pinfunction "P$2_V2") (pintype "bidirectional"))
      (node (ref "B32") (pin "K2") (pinfunction "I$1_K2") (pintype "input"))
    )
    (net (code "243") (name "RUN") (class "Default")
      (node (ref "A06") (pin "S2") (pinfunction "P$2_S2") (pintype "bidirectional"))
      (node (ref "B06") (pin "S2") (pinfunction "P$2_S2") (pintype "bidirectional"))
    )
    (net (code "244") (name "T2") (class "Default")
      (node (ref "A02") (pin "T2") (pinfunction "P$2_T2") (pintype "bidirectional"))
      (node (ref "B02") (pin "T2") (pinfunction "P$2_T2") (pintype "bidirectional"))
      (node (ref "B32") (pin "U2") (pinfunction "I$1_U2") (pintype "input"))
    )
    (net (code "246") (name "WCOV") (class "Default")
      (node (ref "A10") (pin "P2") (pinfunction "P$2_P2") (pintype "bidirectional"))
      (node (ref "A27") (pin "E2") (pinfunction "I$2_E2") (pintype "input"))
      (node (ref "A27") (pin "L2") (pinfunction "I$2_L2") (pintype "input"))
    )
    (net (code "247") (name "WCOV0") (class "Default")
      (node (ref "B10") (pin "P2") (pinfunction "P$2_P2") (pintype "bidirectional"))
      (node (ref "B28") (pin "U2") (pinfunction "H_U2") (pintype "output"))
    )
    (net (code "248") (name "WCOV1") (class "Default")
      (node (ref "B15") (pin "P2") (pinfunction "P$2_P2") (pintype "bidirectional"))
      (node (ref "B29") (pin "V2") (pinfunction "M_V2") (pintype "output"))
    )
    (net (code "249") (name "unconnected-(A12I-I$2-PadV2)") (class "Default")
      (node (ref "A12") (pin "V2") (pinfunction "I$2_V2") (pintype "passive"))
    )
    (net (code "250") (name "unconnected-(A13I-I$2-PadV2)") (class "Default")
      (node (ref "A13") (pin "V2") (pinfunction "I$2_V2") (pintype "passive"))
    )
    (net (code "251") (name "unconnected-(A14I-I$2-PadV2)") (class "Default")
      (node (ref "A14") (pin "V2") (pinfunction "I$2_V2") (pintype "passive"))
    )
    (net (code "252") (name "unconnected-(A25I-I$2-PadV2)") (class "Default")
      (node (ref "A25") (pin "V2") (pinfunction "I$2_V2") (pintype "passive"))
    )
    (net (code "253") (name "unconnected-(A26C-I$3-PadF2)") (class "Default")
      (node (ref "A26") (pin "F2") (pinfunction "I$3_F2") (pintype "passive"))
    )
    (net (code "254") (name "unconnected-(A26E-I$3-PadM2)") (class "Default")
      (node (ref "A26") (pin "M2") (pinfunction "I$3_M2") (pintype "passive"))
    )
    (net (code "255") (name "unconnected-(A26G-I$3-PadT2)") (class "Default")
      (node (ref "A26") (pin "T2") (pinfunction "I$3_T2") (pintype "passive"))
    )
    (net (code "256") (name "unconnected-(A27C-I$3-PadF2)") (class "Default")
      (node (ref "A27") (pin "F2") (pinfunction "I$3_F2") (pintype "passive"))
    )
    (net (code "257") (name "unconnected-(A27E-I$3-PadM2)") (class "Default")
      (node (ref "A27") (pin "M2") (pinfunction "I$3_M2") (pintype "passive"))
    )
    (net (code "258") (name "unconnected-(A27G-I$2-PadS2)") (class "Default")
      (node (ref "A27") (pin "S2") (pinfunction "I$2_S2") (pintype "input"))
    )
    (net (code "259") (name "unconnected-(A27G-I$3-PadT2)") (class "Default")
      (node (ref "A27") (pin "T2") (pinfunction "I$3_T2") (pintype "passive"))
    )
    (net (code "260") (name "unconnected-(A28C-1-PadJ2)") (class "Default")
      (node (ref "A28") (pin "J2") (pinfunction "1_J2") (pintype "open_collector"))
    )
    (net (code "261") (name "unconnected-(A28C-SET-PadM2)") (class "Default")
      (node (ref "A28") (pin "M2") (pinfunction "SET_M2") (pintype "passive"))
    )
    (net (code "262") (name "unconnected-(A31I-I$2-PadV2)") (class "Default")
      (node (ref "A31") (pin "V2") (pinfunction "I$2_V2") (pintype "passive"))
    )
    (net (code "263") (name "unconnected-(A32A-D-PadD2)") (class "Default")
      (node (ref "A32") (pin "D2") (pinfunction "D_D2") (pintype "input"))
    )
    (net (code "264") (name "unconnected-(A32A-E-PadE2)") (class "Default")
      (node (ref "A32") (pin "E2") (pinfunction "E_E2") (pintype "input"))
    )
    (net (code "265") (name "unconnected-(A32A-H-PadH2)") (class "Default")
      (node (ref "A32") (pin "H2") (pinfunction "H_H2") (pintype "input"))
    )
    (net (code "266") (name "unconnected-(A32A-J-PadJ2)") (class "Default")
      (node (ref "A32") (pin "J2") (pinfunction "J_J2") (pintype "input"))
    )
    (net (code "267") (name "unconnected-(A32A-K-PadK2)") (class "Default")
      (node (ref "A32") (pin "K2") (pinfunction "K_K2") (pintype "input"))
    )
    (net (code "268") (name "unconnected-(A32A-N-PadN2)") (class "Default")
      (node (ref "A32") (pin "N2") (pinfunction "N_N2") (pintype "output"))
    )
    (net (code "269") (name "unconnected-(A32A-P-PadP2)") (class "Default")
      (node (ref "A32") (pin "P2") (pinfunction "P_P2") (pintype "output"))
    )
    (net (code "270") (name "unconnected-(A32A-R-PadR2)") (class "Default")
      (node (ref "A32") (pin "R2") (pinfunction "R_R2") (pintype "output"))
    )
    (net (code "271") (name "unconnected-(A32A-T-PadT2)") (class "Default")
      (node (ref "A32") (pin "T2") (pinfunction "T_T2") (pintype "output"))
    )
    (net (code "272") (name "unconnected-(A32A-U-PadU2)") (class "Default")
      (node (ref "A32") (pin "U2") (pinfunction "U_U2") (pintype "output"))
    )
    (net (code "273") (name "unconnected-(B25I-I$2-PadV2)") (class "Default")
      (node (ref "B25") (pin "V2") (pinfunction "I$2_V2") (pintype "passive"))
    )
    (net (code "274") (name "unconnected-(B26A-EN0-PadE2)") (class "Default")
      (node (ref "B26") (pin "E2") (pinfunction "EN0_E2") (pintype "passive"))
    )
    (net (code "275") (name "unconnected-(B26A-PU0-PadD2)") (class "Default")
      (node (ref "B26") (pin "D2") (pinfunction "PU0_D2") (pintype "input"))
    )
    (net (code "276") (name "unconnected-(B26D-I$1-PadP2)") (class "Default")
      (node (ref "B26") (pin "P2") (pinfunction "I$1_P2") (pintype "passive"))
    )
    (net (code "277") (name "unconnected-(B26E-I$1-PadV2)") (class "Default")
      (node (ref "B26") (pin "V2") (pinfunction "I$1_V2") (pintype "passive"))
    )
    (net (code "278") (name "unconnected-(B27C-SET-PadM2)") (class "Default")
      (node (ref "B27") (pin "M2") (pinfunction "SET_M2") (pintype "passive"))
    )
    (net (code "279") (name "unconnected-(B27D-0-PadS2)") (class "Default")
      (node (ref "B27") (pin "S2") (pinfunction "0_S2") (pintype "open_collector"))
    )
    (net (code "280") (name "unconnected-(B28A-E-PadE2)") (class "Default")
      (node (ref "B28") (pin "E2") (pinfunction "E_E2") (pintype "passive"))
    )
    (net (code "281") (name "unconnected-(B28A-F-PadF2)") (class "Default")
      (node (ref "B28") (pin "F2") (pinfunction "F_F2") (pintype "passive"))
    )
    (net (code "282") (name "unconnected-(B28B-E-PadL2)") (class "Default")
      (node (ref "B28") (pin "L2") (pinfunction "E_L2") (pintype "passive"))
    )
    (net (code "283") (name "unconnected-(B28B-F-PadM2)") (class "Default")
      (node (ref "B28") (pin "M2") (pinfunction "F_M2") (pintype "passive"))
    )
    (net (code "284") (name "unconnected-(B28C-E-PadS2)") (class "Default")
      (node (ref "B28") (pin "S2") (pinfunction "E_S2") (pintype "passive"))
    )
    (net (code "285") (name "unconnected-(B28C-F-PadT2)") (class "Default")
      (node (ref "B28") (pin "T2") (pinfunction "F_T2") (pintype "passive"))
    )
    (net (code "286") (name "unconnected-(B29C-H-PadH2)") (class "Default")
      (node (ref "B29") (pin "H2") (pinfunction "H_H2") (pintype "passive"))
    )
    (net (code "287") (name "unconnected-(B29C-L-PadL2)") (class "Default")
      (node (ref "B29") (pin "L2") (pinfunction "L_L2") (pintype "passive"))
    )
    (net (code "288") (name "unconnected-(B29D-H-PadR2)") (class "Default")
      (node (ref "B29") (pin "R2") (pinfunction "H_R2") (pintype "passive"))
    )
    (net (code "289") (name "unconnected-(B29D-L-PadU2)") (class "Default")
      (node (ref "B29") (pin "U2") (pinfunction "L_U2") (pintype "passive"))
    )
    (net (code "290") (name "unconnected-(B30C-I$3-PadF2)") (class "Default")
      (node (ref "B30") (pin "F2") (pinfunction "I$3_F2") (pintype "passive"))
    )
    (net (code "291") (name "unconnected-(B30E-I$3-PadM2)") (class "Default")
      (node (ref "B30") (pin "M2") (pinfunction "I$3_M2") (pintype "passive"))
    )
    (net (code "292") (name "unconnected-(B31C-SET-PadM2)") (class "Default")
      (node (ref "B31") (pin "M2") (pinfunction "SET_M2") (pintype "passive"))
    )
    (net (code "293") (name "unconnected-(B31D-0-PadS2)") (class "Default")
      (node (ref "B31") (pin "S2") (pinfunction "0_S2") (pintype "open_collector"))
    )
    (net (code "294") (name "unconnected-(B32I-I$2-PadV2)") (class "Default")
      (node (ref "B32") (pin "V2") (pinfunction "I$2_V2") (pintype "passive"))
    )
    (net (code "295") (name "~{-BMB3}") (class "Default")
      (node (ref "A03") (pin "K2") (pinfunction "P$2_K2") (pintype "bidirectional"))
      (node (ref "B03") (pin "K2") (pinfunction "P$2_K2") (pintype "bidirectional"))
    )
    (net (code "296") (name "~{-BMB4}") (class "Default")
      (node (ref "A03") (pin "P2") (pinfunction "P$2_P2") (pintype "bidirectional"))
      (node (ref "B03") (pin "P2") (pinfunction "P$2_P2") (pintype "bidirectional"))
    )
    (net (code "297") (name "~{-BMB5}") (class "Default")
      (node (ref "A03") (pin "T2") (pinfunction "P$2_T2") (pintype "bidirectional"))
      (node (ref "B03") (pin "T2") (pinfunction "P$2_T2") (pintype "bidirectional"))
    )
    (net (code "298") (name "~{-BMB6}") (class "Default")
      (node (ref "A04") (pin "D2") (pinfunction "P$2_D2") (pintype "bidirectional"))
      (node (ref "B04") (pin "D2") (pinfunction "P$2_D2") (pintype "bidirectional"))
    )
    (net (code "299") (name "~{-BMB7}") (class "Default")
      (node (ref "A04") (pin "H2") (pinfunction "P$2_H2") (pintype "bidirectional"))
      (node (ref "B04") (pin "H2") (pinfunction "P$2_H2") (pintype "bidirectional"))
    )
    (net (code "300") (name "~{-BMB8}") (class "Default")
      (node (ref "A04") (pin "M2") (pinfunction "P$2_M2") (pintype "bidirectional"))
      (node (ref "B04") (pin "M2") (pinfunction "P$2_M2") (pintype "bidirectional"))
    )
    (net (code "301") (name "~{BREAK}") (class "Default")
      (node (ref "A27") (pin "U2") (pinfunction "O$1_U2") (pintype "open_collector"))
      (node (ref "A27") (pin "V2") (pinfunction "P$1_V2") (pintype "passive"))
      (node (ref "B26") (pin "S2") (pinfunction "EN0_S2") (pintype "passive"))
    )
    (net (code "302") (name "~{BRK_SYNC_CLK}") (class "Default")
      (node (ref "A25") (pin "T2") (pinfunction "O$1_T2") (pintype "open_collector"))
      (node (ref "PDP-12") (pin "2") (pinfunction "2_2") (pintype "passive"))
    )
  )
)
